# permamote.net
KiCad netlist of a schematic drawn in EAGLE
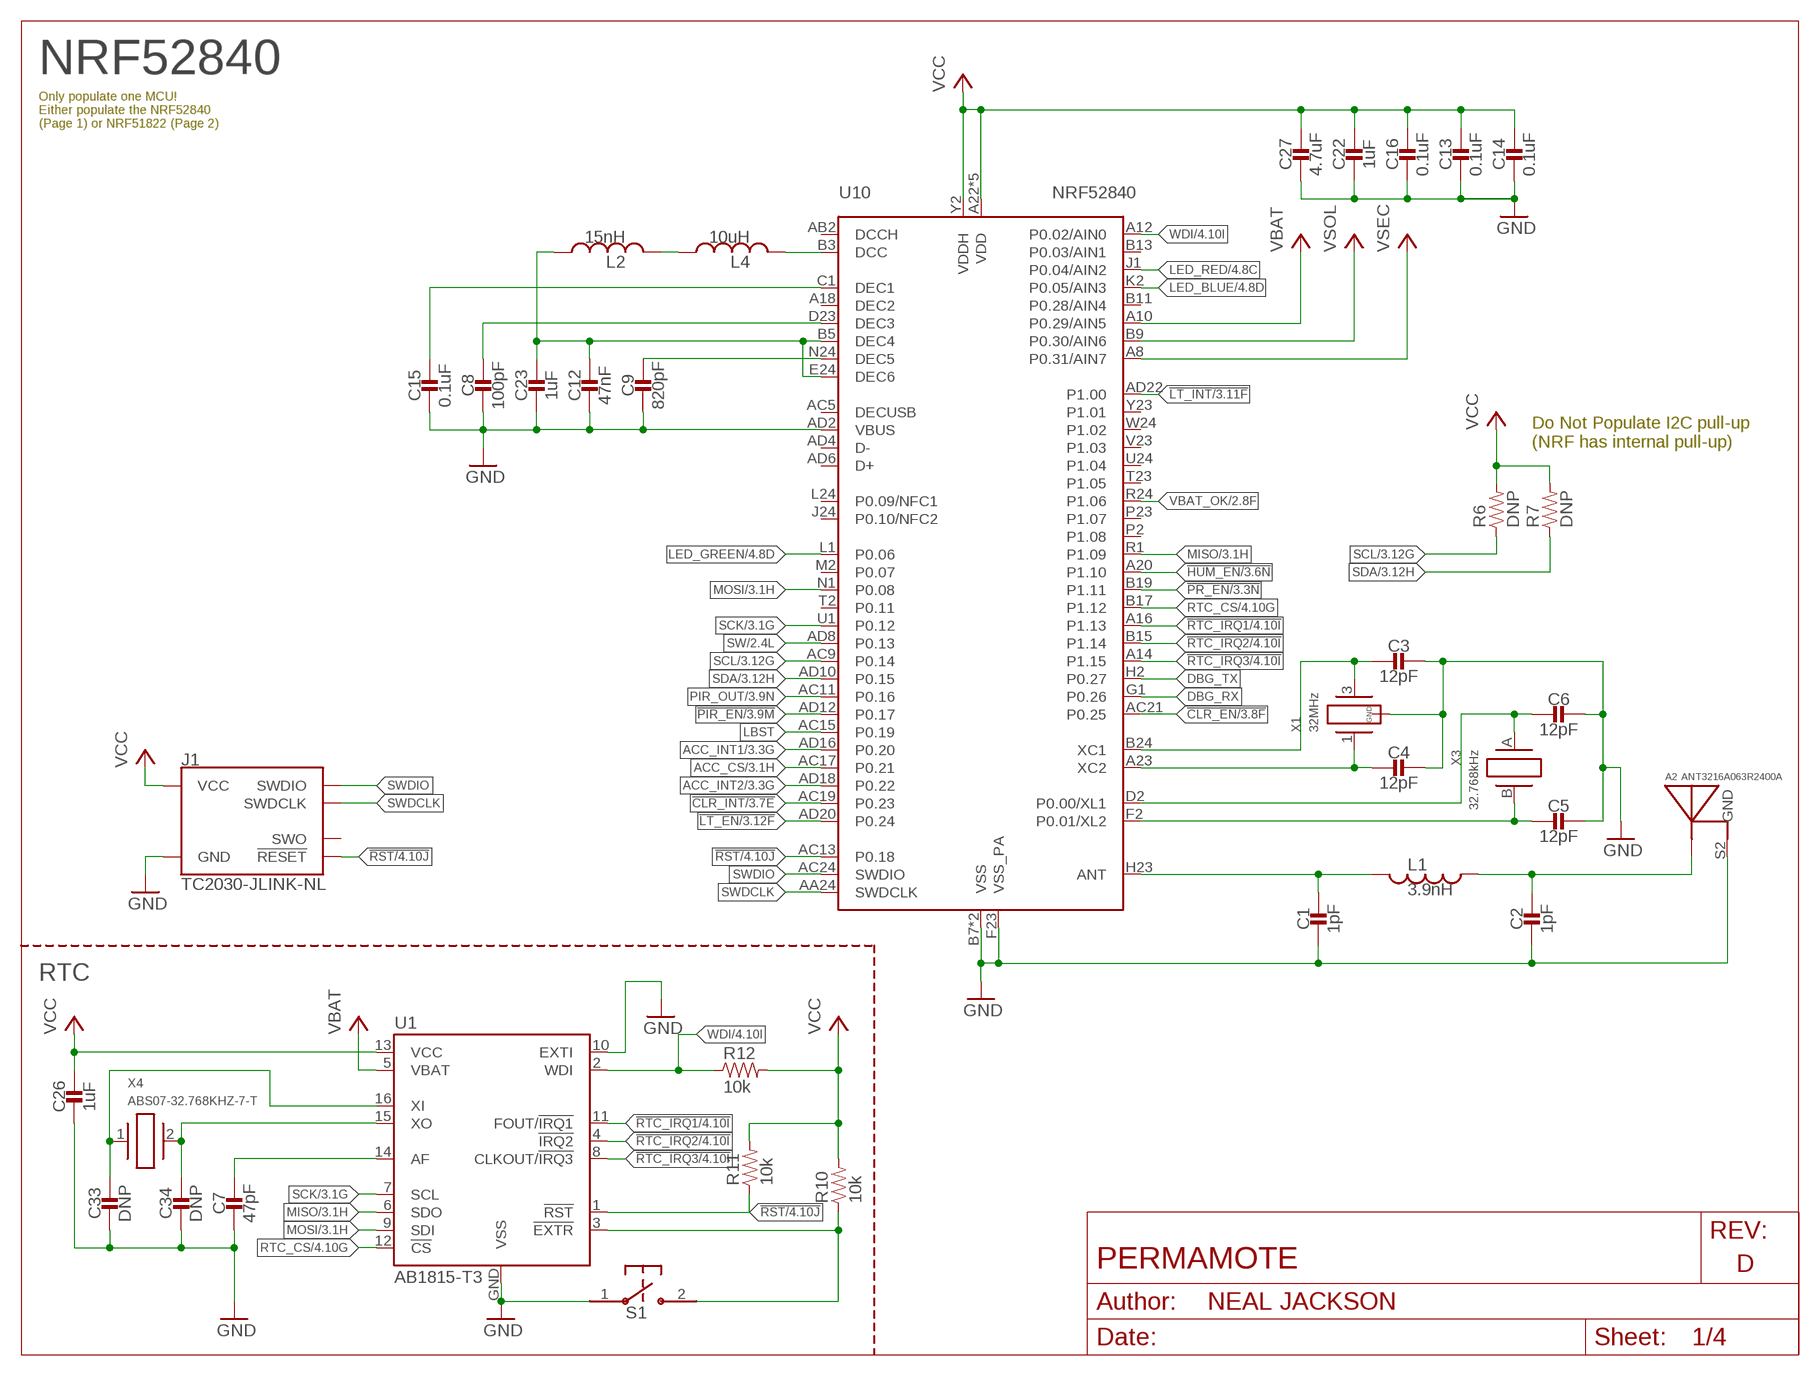
[diagram p0: schematic, sheet 1]
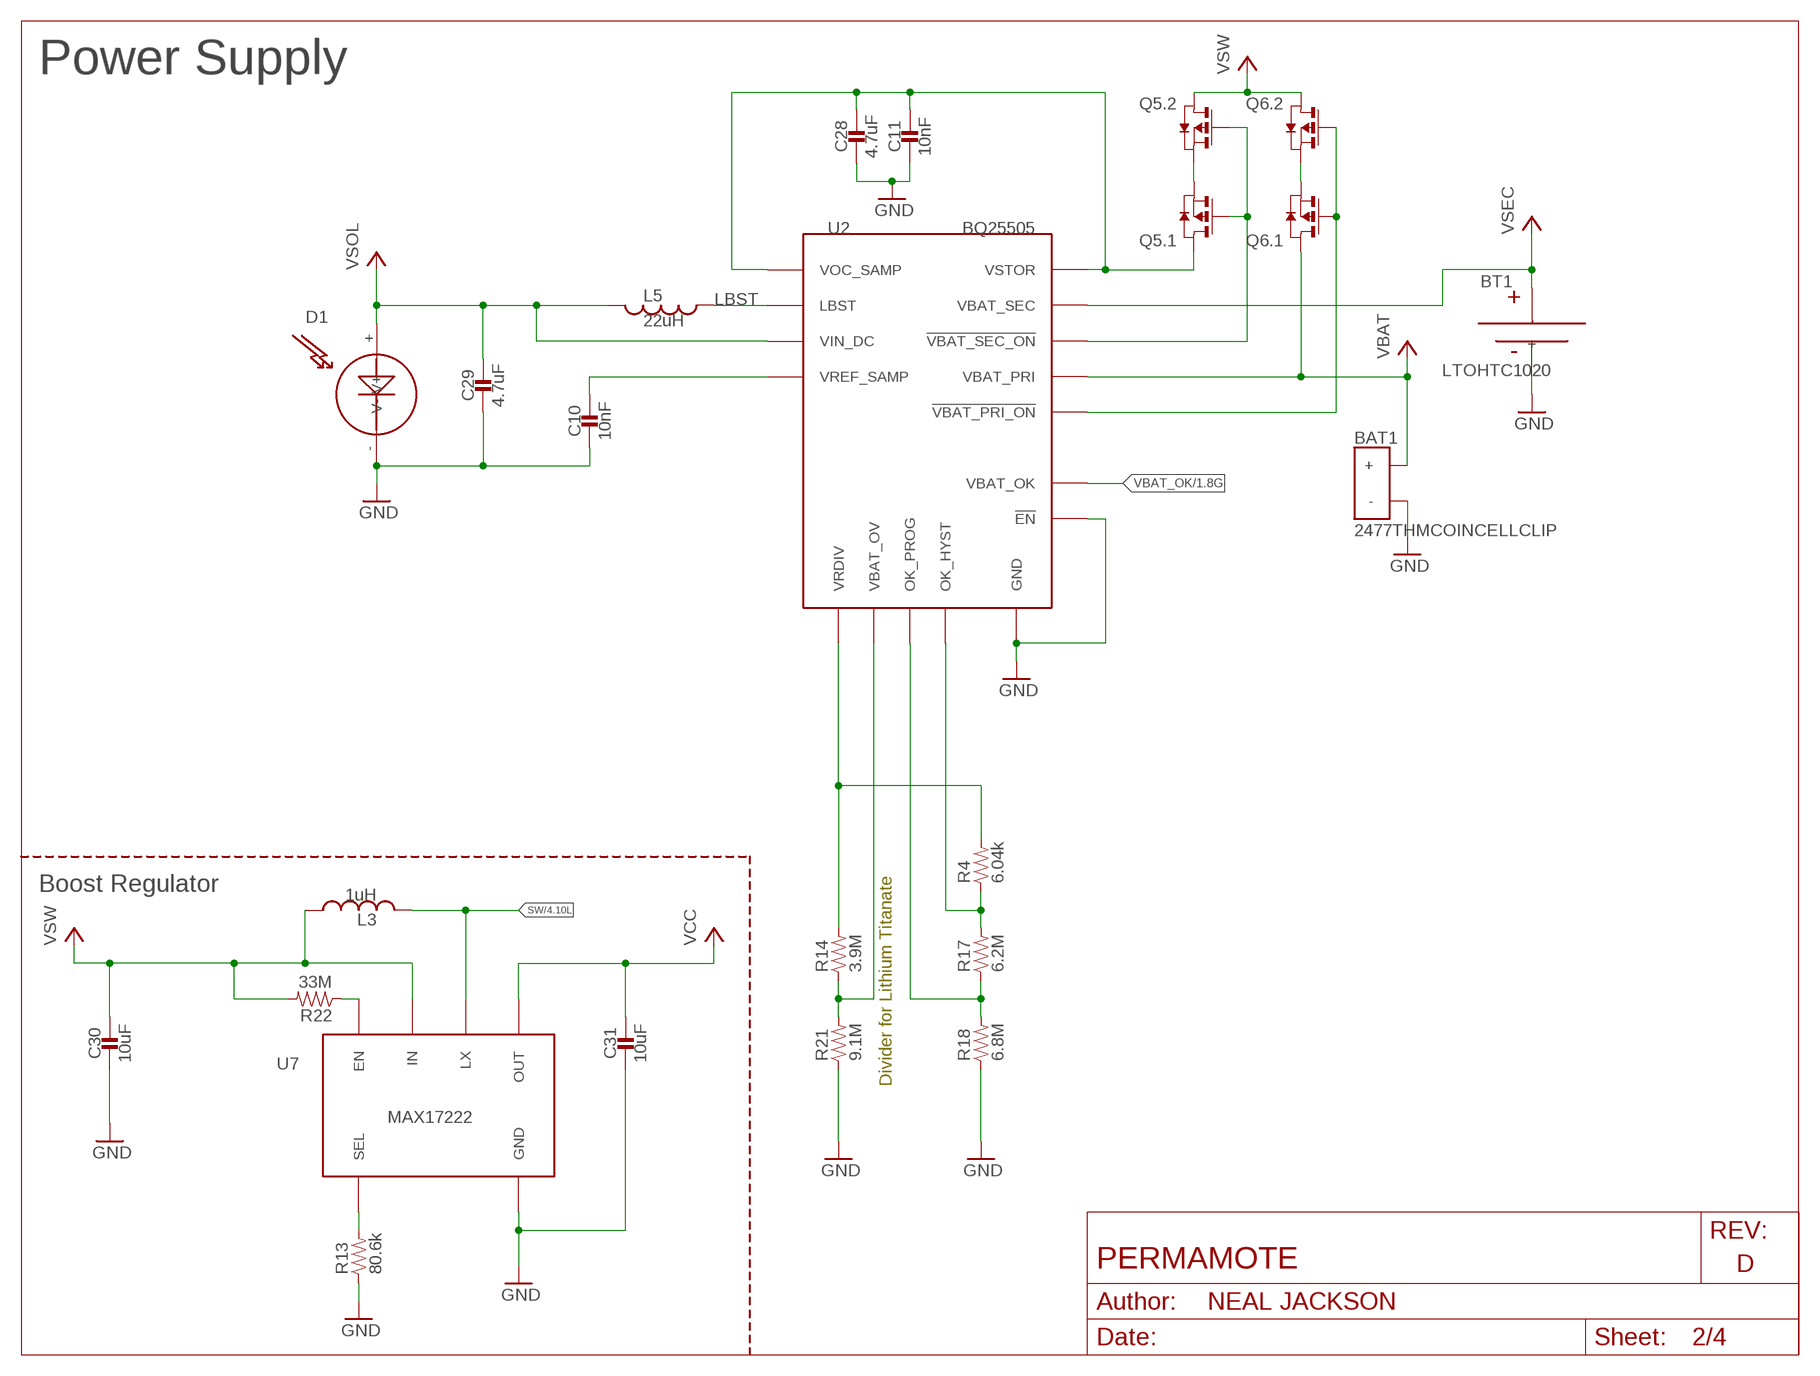
[diagram p1: schematic, sheet 2]
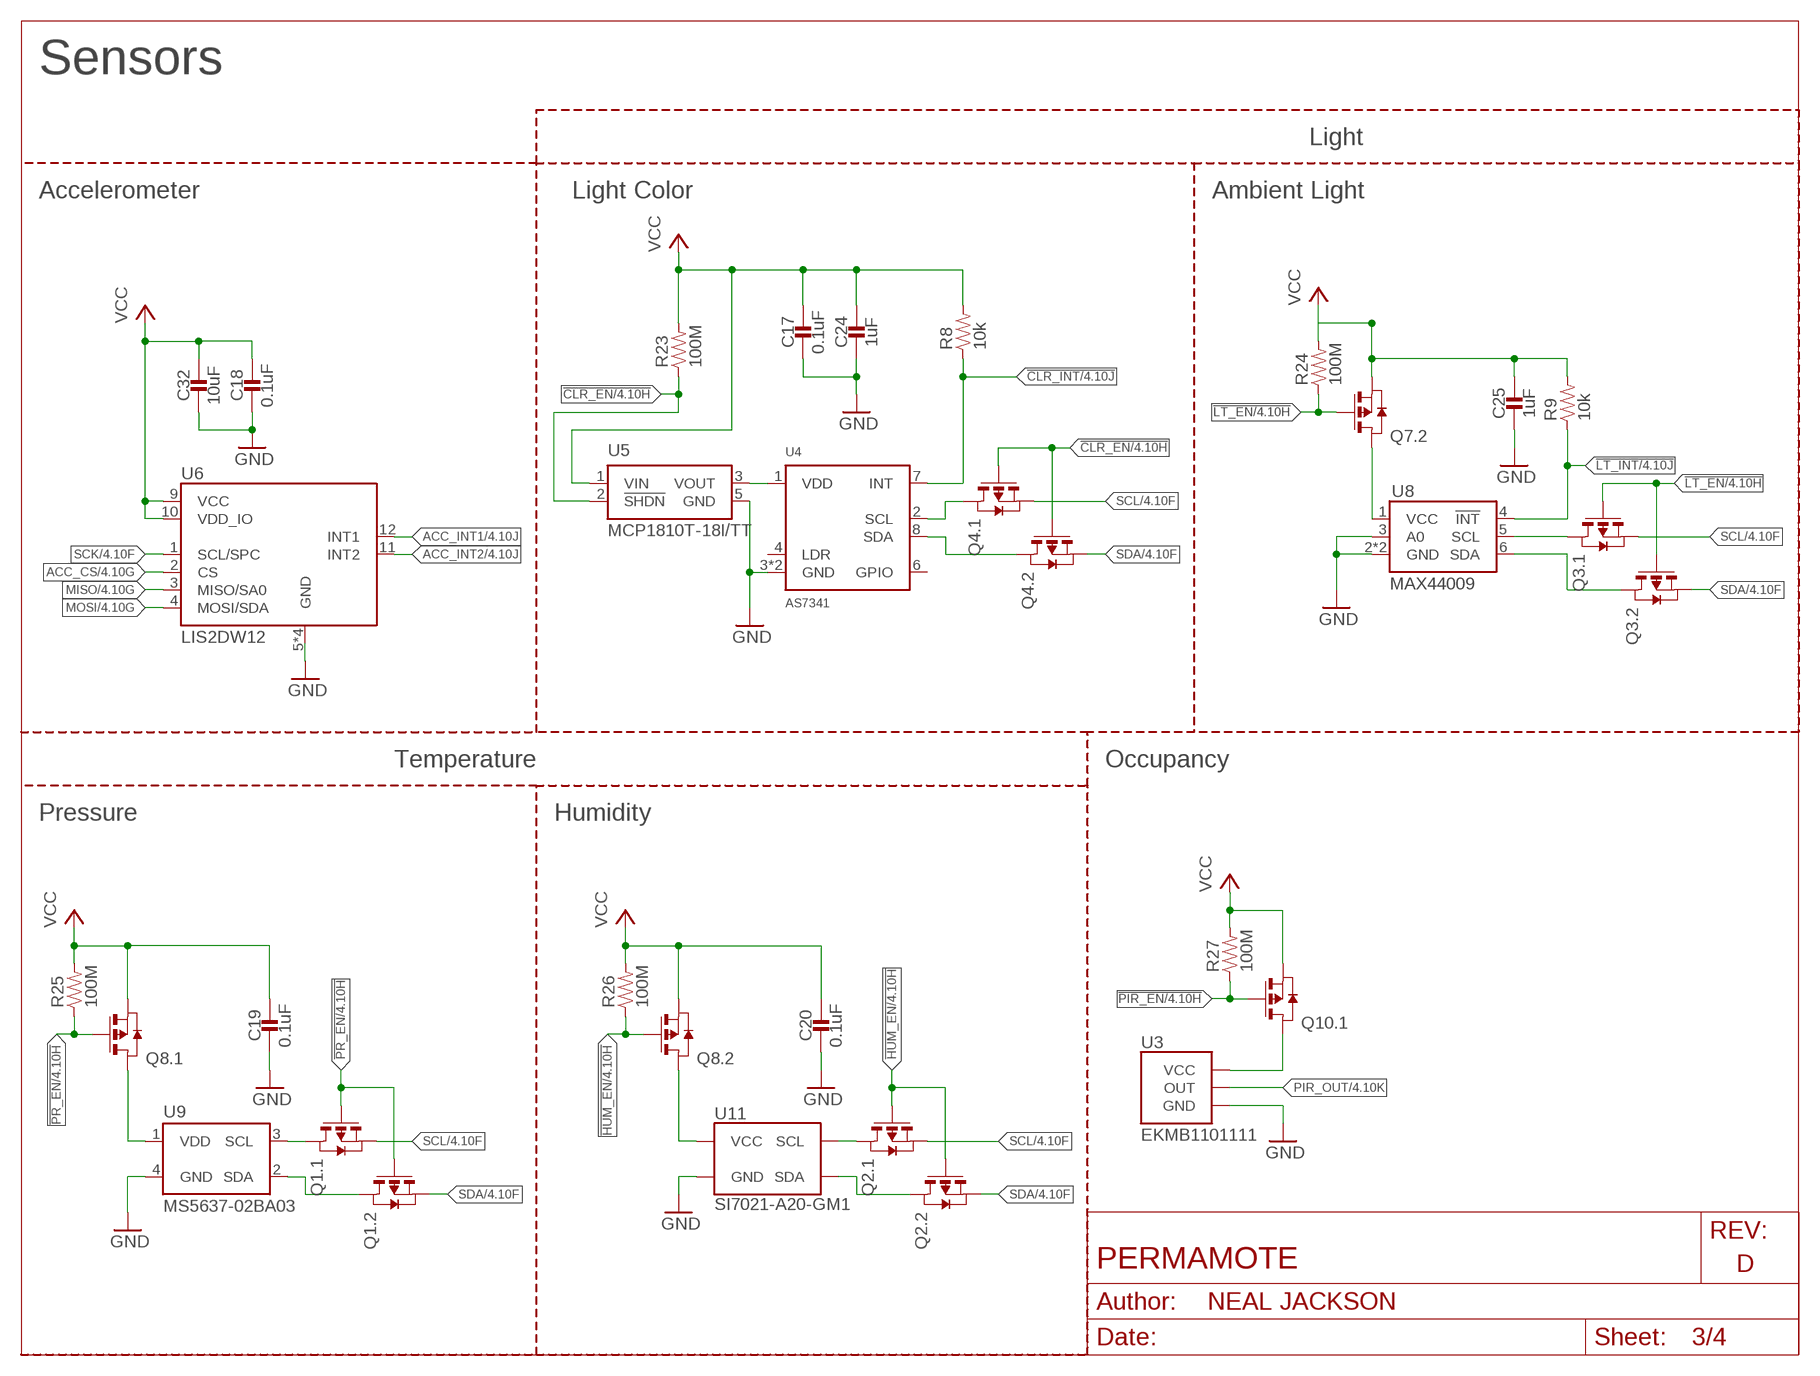
[diagram p2: schematic, sheet 3]
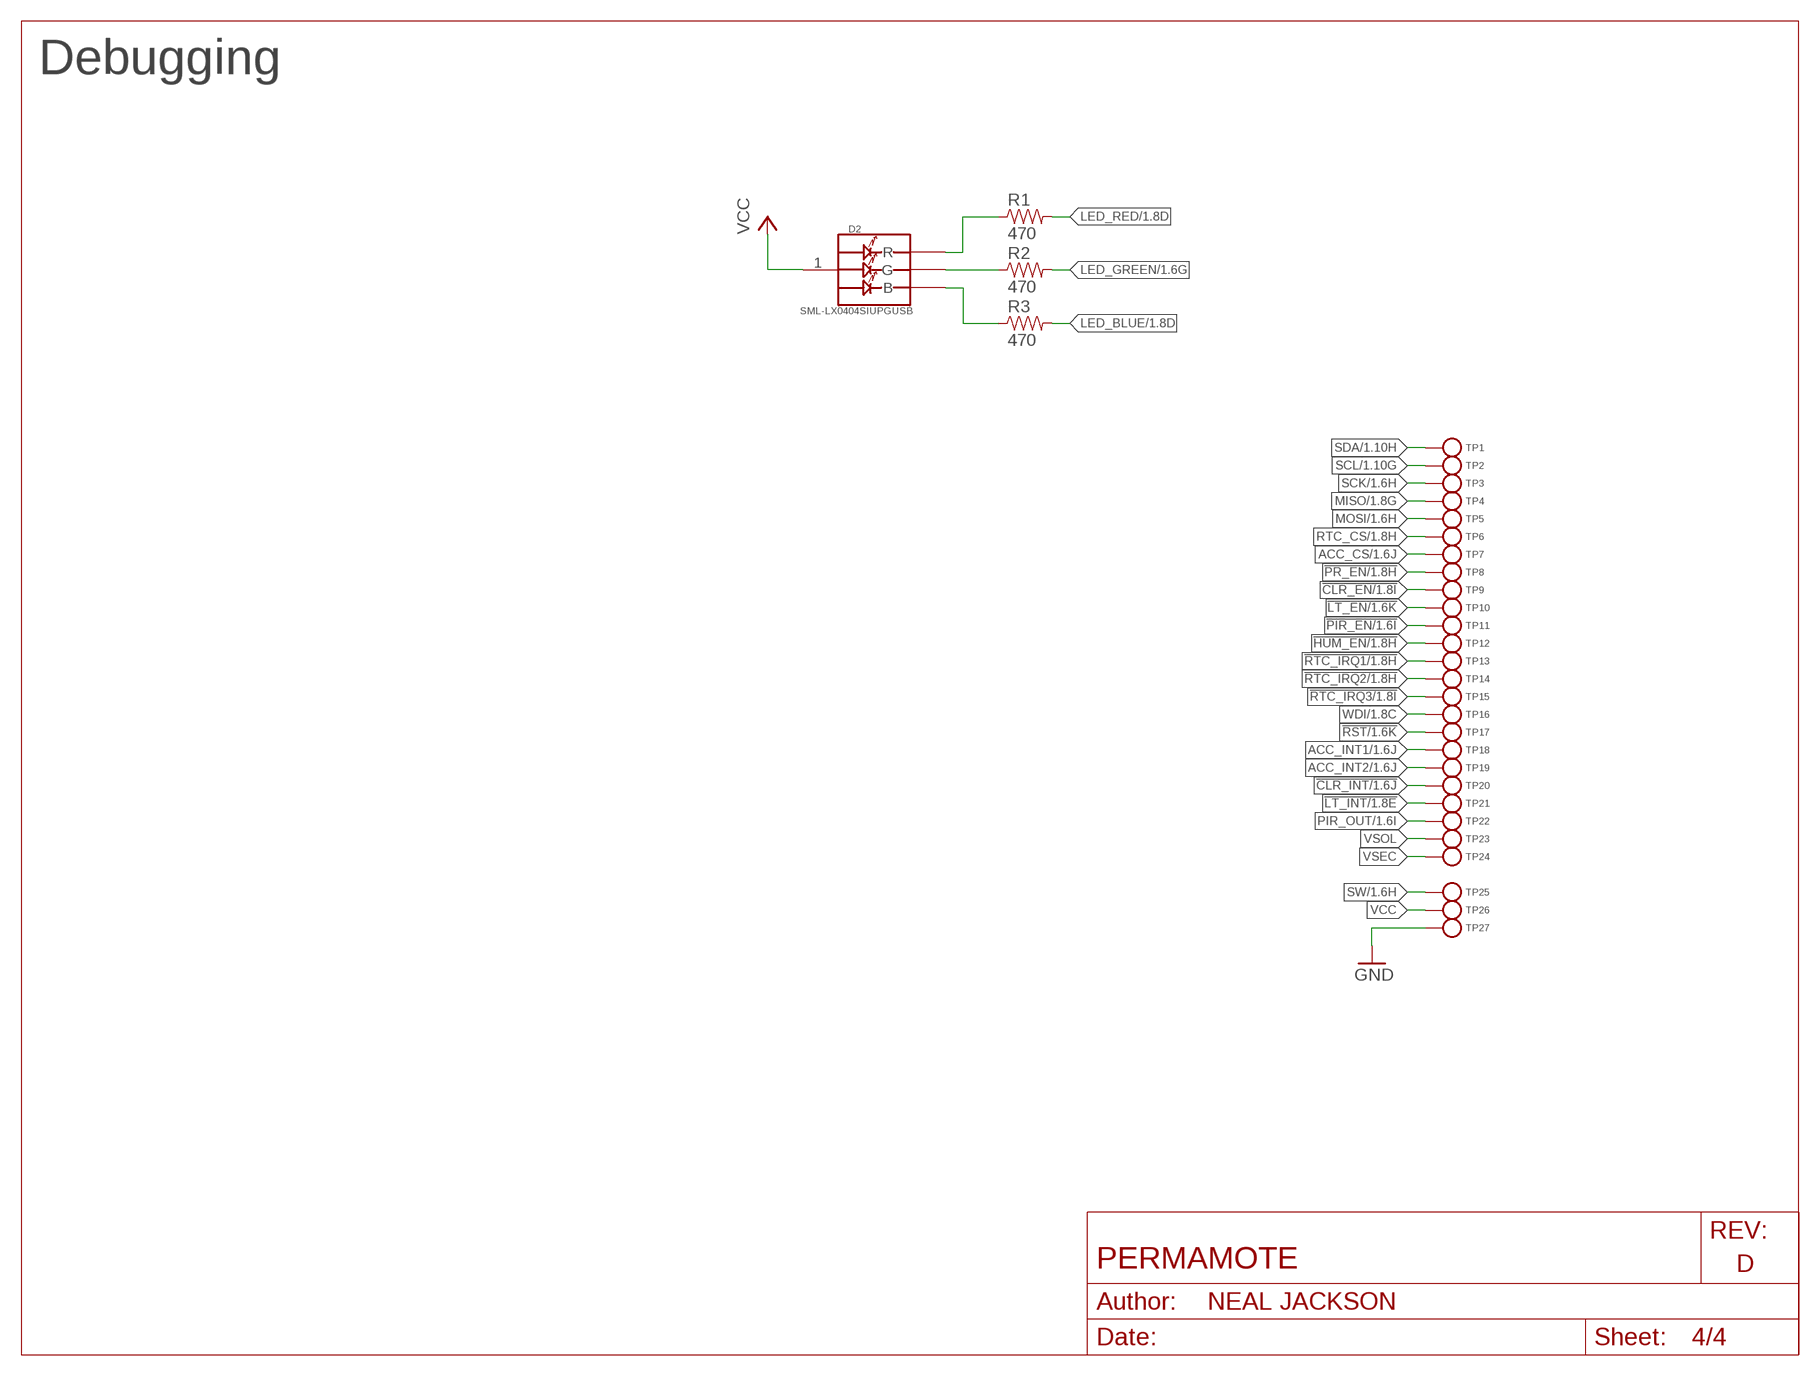
[diagram p3: schematic, sheet 4]

(export (version "E")
  (design (tool "Eeschema 10.0.6"))
  (components
    (comp (ref "BAT1")
      (value "2477THMCOINCELLCLIP")
      (footprint "eagle-import:2477THMCOINCLIP")
      (fields (field (name "MANUFACTURER") "Keystone") (field (name "MPN") "3039"))
      (libsource (lib "eagle-import") (part "2477THMCOINCELLCLIP"))
    )
    (comp (ref "BT1")
      (value "LTOHTC1020")
      (footprint "eagle-import:1020")
      (libsource (lib "eagle-import") (part "LTOHTC1020"))
    )
    (comp (ref "C10")
      (value "10nF")
      (footprint "eagle-import:0402_CAP")
      (fields (field (name "MPN") "GRM155R71H103KA88D "))
      (libsource (lib "eagle-import") (part "CAPACITOR0402_CAP"))
    )
    (comp (ref "C11")
      (value "10nF")
      (footprint "eagle-import:0402_CAP")
      (fields (field (name "MPN") "GRM155R71H103KA88D "))
      (libsource (lib "eagle-import") (part "CAPACITOR0402_CAP"))
    )
    (comp (ref "C28")
      (value "4.7uF")
      (footprint "eagle-import:0402_CAP")
      (fields (field (name "MPN") "C1005X5R0J475K050BC "))
      (libsource (lib "eagle-import") (part "CAPACITOR0402_CAP"))
    )
    (comp (ref "C29")
      (value "4.7uF")
      (footprint "eagle-import:0402_CAP")
      (fields (field (name "MPN") "C1005X5R0J475K050BC "))
      (libsource (lib "eagle-import") (part "CAPACITOR0402_CAP"))
    )
    (comp (ref "C30")
      (value "10uF")
      (footprint "eagle-import:0603_CAP")
      (fields (field (name "MPN") "GRM188R60J106ME47D "))
      (libsource (lib "eagle-import") (part "CAPACITOR0603_CAP"))
    )
    (comp (ref "C31")
      (value "10uF")
      (footprint "eagle-import:0603_CAP")
      (fields (field (name "MPN") "GRM188R60J106ME47D "))
      (libsource (lib "eagle-import") (part "CAPACITOR0603_CAP"))
    )
    (comp (ref "D1")
      (value "SOLARCELLHOLES")
      (footprint "eagle-import:SOLAR_HOLES")
      (fields (field (name "MPN") "AM-1454CA"))
      (libsource (lib "eagle-import") (part "SOLARCELLHOLES"))
    )
    (comp (ref "L3")
      (value "1uH")
      (footprint "eagle-import:IHL-1212BZ-11")
      (fields
        (field (name "MANUFACTURER") "Vishay Dale")
        (field (name "MPN") "IHLP1212BZER2R2M11")
        (field (name "DIGIKEY") "541-1319-1-ND")
        (field (name "MPN_1") "IHLP1212BZER1R0M11")
      )
      (libsource (lib "eagle-import") (part "INDUCTORIHL"))
    )
    (comp (ref "L5")
      (value "22uH")
      (footprint "eagle-import:74437324220")
      (fields (field (name "DIGIKEY") "732-3340-1-ND") (field (name "MPN") "74437324220 "))
      (libsource (lib "eagle-import") (part "INDUCTOR74437324220"))
    )
    (comp (ref "Q5")
      (value "PMDXB950UPEL")
      (footprint "eagle-import:XDFN-6")
      (fields (field (name "MANUFACTURER") "NEXPERIA") (field (name "MPN") "PMDXB950UPELZ"))
      (libsource (lib "eagle-import") (part "PMDXB950UPEL"))
    )
    (comp (ref "Q6")
      (value "PMDXB950UPEL")
      (footprint "eagle-import:XDFN-6")
      (fields (field (name "MANUFACTURER") "NEXPERIA") (field (name "MPN") "PMDXB950UPELZ"))
      (libsource (lib "eagle-import") (part "PMDXB950UPEL"))
    )
    (comp (ref "R4")
      (value "6.04k")
      (footprint "eagle-import:0402_RES")
      (fields (field (name "MPN") "RC0402FR-076K04L"))
      (libsource (lib "eagle-import") (part "RESISTOR0402_RES"))
    )
    (comp (ref "R13")
      (value "80.6k")
      (footprint "eagle-import:0603-RES")
      (fields (field (name "MPN") "RC0603FR-0780K6L "))
      (libsource (lib "eagle-import") (part "RESISTOR0603_RES"))
    )
    (comp (ref "R14")
      (value "3.9M")
      (footprint "eagle-import:0402_RES")
      (fields (field (name "MPN") "RC0402JR-073M9L"))
      (libsource (lib "eagle-import") (part "RESISTOR0402_RES"))
    )
    (comp (ref "R17")
      (value "6.2M")
      (footprint "eagle-import:0402_RES")
      (fields (field (name "MPN") "RC0402JR-076M2L"))
      (libsource (lib "eagle-import") (part "RESISTOR0402_RES"))
    )
    (comp (ref "R18")
      (value "6.8M")
      (footprint "eagle-import:0402_RES")
      (fields (field (name "MPN") "RC0402JR-076M8L"))
      (libsource (lib "eagle-import") (part "RESISTOR0402_RES"))
    )
    (comp (ref "R21")
      (value "9.1M")
      (footprint "eagle-import:0402_RES")
      (fields (field (name "MPN") "RC0402JR-079M1L"))
      (libsource (lib "eagle-import") (part "RESISTOR0402_RES"))
    )
    (comp (ref "R22")
      (value "33M")
      (footprint "eagle-import:0603-RES")
      (fields (field (name "MPN") "HMC0603JT33M0 "))
      (libsource (lib "eagle-import") (part "RESISTOR0603_RES"))
    )
    (comp (ref "U2")
      (value "BQ25505")
      (footprint "eagle-import:S-PVQFN-N20-RGR")
      (fields (field (name "MANUFACTURER") "TI") (field (name "MPN") "BQ25505RGRR"))
      (libsource (lib "eagle-import") (part "BQ25505"))
    )
    (comp (ref "U7")
      (value "MAX17222")
      (footprint "eagle-import:UDFN-6-MAXIM")
      (fields (field (name "MANUFACTURER") "MAXIM INTEGRATED") (field (name "MPN") "MAX17222ELT+T"))
      (libsource (lib "eagle-import") (part "MAX17222"))
    )
    (comp (ref "D2")
      (value "SML-LX0404SIUPGUSB")
      (footprint "eagle-import:1MM_SQ_4PAD")
      (fields (field (name "MANUFACTURER") "Lumex Opto"))
      (libsource (lib "eagle-import") (part "SML-LX0404SIUPGUSB"))
    )
    (comp (ref "R1")
      (value "470")
      (footprint "eagle-import:0402_RES")
      (fields (field (name "MPN") "RC0402JR-07470RL "))
      (libsource (lib "eagle-import") (part "RESISTOR0402_RES"))
    )
    (comp (ref "R2")
      (value "470")
      (footprint "eagle-import:0402_RES")
      (fields (field (name "MPN") "RC0402JR-07470RL "))
      (libsource (lib "eagle-import") (part "RESISTOR0402_RES"))
    )
    (comp (ref "R3")
      (value "470")
      (footprint "eagle-import:0402_RES")
      (fields (field (name "MPN") "RC0402JR-07470RL "))
      (libsource (lib "eagle-import") (part "RESISTOR0402_RES"))
    )
    (comp (ref "TP1")
      (value "TEST-POINT")
      (footprint "eagle-import:PAD.03X.03")
      (libsource (lib "eagle-import") (part "TEST-POINT"))
    )
    (comp (ref "TP2")
      (value "TEST-POINT")
      (footprint "eagle-import:PAD.03X.03")
      (libsource (lib "eagle-import") (part "TEST-POINT"))
    )
    (comp (ref "TP3")
      (value "TEST-POINT")
      (footprint "eagle-import:PAD.03X.03")
      (libsource (lib "eagle-import") (part "TEST-POINT"))
    )
    (comp (ref "TP4")
      (value "TEST-POINT")
      (footprint "eagle-import:PAD.03X.03")
      (libsource (lib "eagle-import") (part "TEST-POINT"))
    )
    (comp (ref "TP5")
      (value "TEST-POINT")
      (footprint "eagle-import:PAD.03X.03")
      (libsource (lib "eagle-import") (part "TEST-POINT"))
    )
    (comp (ref "TP6")
      (value "TEST-POINT")
      (footprint "eagle-import:PAD.03X.03")
      (libsource (lib "eagle-import") (part "TEST-POINT"))
    )
    (comp (ref "TP7")
      (value "TEST-POINT")
      (footprint "eagle-import:PAD.03X.03")
      (libsource (lib "eagle-import") (part "TEST-POINT"))
    )
    (comp (ref "TP8")
      (value "TEST-POINT")
      (footprint "eagle-import:PAD.03X.03")
      (libsource (lib "eagle-import") (part "TEST-POINT"))
    )
    (comp (ref "TP9")
      (value "TEST-POINT")
      (footprint "eagle-import:PAD.03X.03")
      (libsource (lib "eagle-import") (part "TEST-POINT"))
    )
    (comp (ref "TP10")
      (value "TEST-POINT")
      (footprint "eagle-import:PAD.03X.03")
      (libsource (lib "eagle-import") (part "TEST-POINT"))
    )
    (comp (ref "TP11")
      (value "TEST-POINT")
      (footprint "eagle-import:PAD.03X.03")
      (libsource (lib "eagle-import") (part "TEST-POINT"))
    )
    (comp (ref "TP12")
      (value "TEST-POINT")
      (footprint "eagle-import:PAD.03X.03")
      (libsource (lib "eagle-import") (part "TEST-POINT"))
    )
    (comp (ref "TP13")
      (value "TEST-POINT")
      (footprint "eagle-import:PAD.03X.03")
      (libsource (lib "eagle-import") (part "TEST-POINT"))
    )
    (comp (ref "TP14")
      (value "TEST-POINT")
      (footprint "eagle-import:PAD.03X.03")
      (libsource (lib "eagle-import") (part "TEST-POINT"))
    )
    (comp (ref "TP15")
      (value "TEST-POINT")
      (footprint "eagle-import:PAD.03X.03")
      (libsource (lib "eagle-import") (part "TEST-POINT"))
    )
    (comp (ref "TP16")
      (value "TEST-POINT")
      (footprint "eagle-import:PAD.03X.03")
      (libsource (lib "eagle-import") (part "TEST-POINT"))
    )
    (comp (ref "TP17")
      (value "TEST-POINT")
      (footprint "eagle-import:PAD.03X.03")
      (libsource (lib "eagle-import") (part "TEST-POINT"))
    )
    (comp (ref "TP18")
      (value "TEST-POINT")
      (footprint "eagle-import:PAD.03X.03")
      (libsource (lib "eagle-import") (part "TEST-POINT"))
    )
    (comp (ref "TP19")
      (value "TEST-POINT")
      (footprint "eagle-import:PAD.03X.03")
      (libsource (lib "eagle-import") (part "TEST-POINT"))
    )
    (comp (ref "TP20")
      (value "TEST-POINT")
      (footprint "eagle-import:PAD.03X.03")
      (libsource (lib "eagle-import") (part "TEST-POINT"))
    )
    (comp (ref "TP21")
      (value "TEST-POINT")
      (footprint "eagle-import:PAD.03X.03")
      (libsource (lib "eagle-import") (part "TEST-POINT"))
    )
    (comp (ref "TP22")
      (value "TEST-POINT")
      (footprint "eagle-import:PAD.03X.03")
      (libsource (lib "eagle-import") (part "TEST-POINT"))
    )
    (comp (ref "TP23")
      (value "TEST-POINT")
      (footprint "eagle-import:PAD.03X.03")
      (libsource (lib "eagle-import") (part "TEST-POINT"))
    )
    (comp (ref "TP24")
      (value "TEST-POINT")
      (footprint "eagle-import:PAD.03X.03")
      (libsource (lib "eagle-import") (part "TEST-POINT"))
    )
    (comp (ref "TP25")
      (value "TEST-POINT")
      (footprint "eagle-import:PAD.03X.03")
      (libsource (lib "eagle-import") (part "TEST-POINT"))
    )
    (comp (ref "TP26")
      (value "TEST-POINT")
      (footprint "eagle-import:PAD.03X.03")
      (libsource (lib "eagle-import") (part "TEST-POINT"))
    )
    (comp (ref "TP27")
      (value "TEST-POINT")
      (footprint "eagle-import:PAD.03X.03")
      (libsource (lib "eagle-import") (part "TEST-POINT"))
    )
    (comp (ref "C17")
      (value "0.1uF")
      (footprint "eagle-import:0402_CAP")
      (fields (field (name "MPN") "GRM155R71C104KA88J "))
      (libsource (lib "eagle-import") (part "CAPACITOR0402_CAP"))
    )
    (comp (ref "C18")
      (value "0.1uF")
      (footprint "eagle-import:0402_CAP")
      (fields (field (name "MPN") "GRM155R71C104KA88J "))
      (libsource (lib "eagle-import") (part "CAPACITOR0402_CAP"))
    )
    (comp (ref "C19")
      (value "0.1uF")
      (footprint "eagle-import:0402_CAP")
      (fields (field (name "MPN") "GRM155R71C104KA88J "))
      (libsource (lib "eagle-import") (part "CAPACITOR0402_CAP"))
    )
    (comp (ref "C20")
      (value "0.1uF")
      (footprint "eagle-import:0402_CAP")
      (fields (field (name "MPN") "GRM155R71C104KA88J "))
      (libsource (lib "eagle-import") (part "CAPACITOR0402_CAP"))
    )
    (comp (ref "C24")
      (value "1uF")
      (footprint "eagle-import:0402_CAP")
      (fields (field (name "MPN") "GRM155R70G105KA12D "))
      (libsource (lib "eagle-import") (part "CAPACITOR0402_CAP"))
    )
    (comp (ref "C25")
      (value "1uF")
      (footprint "eagle-import:0402_CAP")
      (fields (field (name "MPN") "GRM155R70G105KA12D "))
      (libsource (lib "eagle-import") (part "CAPACITOR0402_CAP"))
    )
    (comp (ref "C32")
      (value "10uF")
      (footprint "eagle-import:0603_CAP")
      (fields (field (name "MPN") "GRM188R60J106ME47D "))
      (libsource (lib "eagle-import") (part "CAPACITOR0603_CAP"))
    )
    (comp (ref "Q1")
      (value "PMDXB950UPEL")
      (footprint "eagle-import:XDFN-6")
      (fields (field (name "MANUFACTURER") "NEXPERIA") (field (name "MPN") "PMDXB950UPELZ"))
      (libsource (lib "eagle-import") (part "PMDXB950UPEL"))
    )
    (comp (ref "Q2")
      (value "PMDXB950UPEL")
      (footprint "eagle-import:XDFN-6")
      (fields (field (name "MANUFACTURER") "NEXPERIA") (field (name "MPN") "PMDXB950UPELZ"))
      (libsource (lib "eagle-import") (part "PMDXB950UPEL"))
    )
    (comp (ref "Q3")
      (value "PMDXB950UPEL")
      (footprint "eagle-import:XDFN-6")
      (fields (field (name "MANUFACTURER") "NEXPERIA") (field (name "MPN") "PMDXB950UPELZ"))
      (libsource (lib "eagle-import") (part "PMDXB950UPEL"))
    )
    (comp (ref "Q4")
      (value "PMDXB950UPEL")
      (footprint "eagle-import:XDFN-6")
      (fields (field (name "MANUFACTURER") "NEXPERIA") (field (name "MPN") "PMDXB950UPELZ"))
      (libsource (lib "eagle-import") (part "PMDXB950UPEL"))
    )
    (comp (ref "Q7")
      (value "PMDXB950UPEL")
      (footprint "eagle-import:XDFN-6")
      (fields (field (name "MANUFACTURER") "NEXPERIA") (field (name "MPN") "PMDXB950UPELZ"))
      (libsource (lib "eagle-import") (part "PMDXB950UPEL"))
    )
    (comp (ref "Q8")
      (value "PMDXB950UPEL")
      (footprint "eagle-import:XDFN-6")
      (fields (field (name "MANUFACTURER") "NEXPERIA") (field (name "MPN") "PMDXB950UPELZ"))
      (libsource (lib "eagle-import") (part "PMDXB950UPEL"))
    )
    (comp (ref "Q10")
      (value "PMDXB950UPEL")
      (footprint "eagle-import:XDFN-6")
      (fields (field (name "MANUFACTURER") "NEXPERIA") (field (name "MPN") "PMDXB950UPELZ"))
      (libsource (lib "eagle-import") (part "PMDXB950UPEL"))
    )
    (comp (ref "R8")
      (value "10k")
      (footprint "eagle-import:0402_RES")
      (fields (field (name "MPN") "RC0402JR-0710KL"))
      (libsource (lib "eagle-import") (part "RESISTOR0402_RES"))
    )
    (comp (ref "R9")
      (value "10k")
      (footprint "eagle-import:0402_RES")
      (fields (field (name "MPN") "RC0402JR-0710KL"))
      (libsource (lib "eagle-import") (part "RESISTOR0402_RES"))
    )
    (comp (ref "R23")
      (value "100M")
      (footprint "eagle-import:0402_RES")
      (fields (field (name "MPN") "HMC0402JT100M "))
      (libsource (lib "eagle-import") (part "RESISTOR0402_RES"))
    )
    (comp (ref "R24")
      (value "100M")
      (footprint "eagle-import:0402_RES")
      (fields (field (name "MPN") "HMC0402JT100M "))
      (libsource (lib "eagle-import") (part "RESISTOR0402_RES"))
    )
    (comp (ref "R25")
      (value "100M")
      (footprint "eagle-import:0402_RES")
      (fields (field (name "MPN") "HMC0402JT100M "))
      (libsource (lib "eagle-import") (part "RESISTOR0402_RES"))
    )
    (comp (ref "R26")
      (value "100M")
      (footprint "eagle-import:0402_RES")
      (fields (field (name "MPN") "HMC0402JT100M "))
      (libsource (lib "eagle-import") (part "RESISTOR0402_RES"))
    )
    (comp (ref "R27")
      (value "100M")
      (footprint "eagle-import:0402_RES")
      (fields (field (name "MPN") "HMC0402JT100M "))
      (libsource (lib "eagle-import") (part "RESISTOR0402_RES"))
    )
    (comp (ref "U3")
      (value "EKMB1101111")
      (footprint "eagle-import:AMN2")
      (fields (field (name "MANUFACTURER") "PANASONIC"))
      (libsource (lib "eagle-import") (part "EKMB1101111"))
    )
    (comp (ref "U4")
      (value "AS7341")
      (footprint "eagle-import:OLGA-8")
      (libsource (lib "eagle-import") (part "AS7341"))
    )
    (comp (ref "U5")
      (value "MCP1810T-18I/TT")
      (footprint "eagle-import:SOT-23-5")
      (libsource (lib "eagle-import") (part "MCP1810T-18I/TT"))
    )
    (comp (ref "U6")
      (value "LIS2DW12")
      (footprint "eagle-import:LGA-12")
      (fields (field (name "MANUFACTURER") "STMicroelectronics") (field (name "MPN") "LIS2DW12TR"))
      (libsource (lib "eagle-import") (part "LIS2DW12"))
    )
    (comp (ref "U8")
      (value "MAX44009")
      (footprint "eagle-import:UDFN-6-EXPOSED")
      (fields (field (name "MANUFACTURER") "MAXIM") (field (name "MPN") "MAX44009EDT+T"))
      (libsource (lib "eagle-import") (part "MAX44009"))
    )
    (comp (ref "U9")
      (value "MS5637-02BA03")
      (footprint "eagle-import:4-SMD")
      (fields (field (name "MANUFACTURER") "TE CONNECTIVITY") (field (name "MPN") "MS563702BA03-50"))
      (libsource (lib "eagle-import") (part "MS5637-02BA03"))
    )
    (comp (ref "U11")
      (value "SI7021-A20-GM1")
      (footprint "eagle-import:DFN-6_3MM")
      (fields (field (name "MPN") "SI7021-A20-GM1 "))
      (libsource (lib "eagle-import") (part "SI7021-A20-GM1"))
    )
    (comp (ref "A2")
      (value "ANT3216A063R2400A")
      (footprint "eagle-import:ANT3216A063R2400A")
      (fields (field (name "MANUFACTURER") "YAGEO"))
      (libsource (lib "eagle-import") (part "ANT3216A063R2400A"))
    )
    (comp (ref "C1")
      (value "1pF")
      (footprint "eagle-import:0402_CAP")
      (fields (field (name "MPN") "CL05C010CB5NNNC"))
      (libsource (lib "eagle-import") (part "CAPACITOR0402_CAP"))
    )
    (comp (ref "C2")
      (value "1pF")
      (footprint "eagle-import:0402_CAP")
      (fields (field (name "MPN") "CL05C010CB5NNNC"))
      (libsource (lib "eagle-import") (part "CAPACITOR0402_CAP"))
    )
    (comp (ref "C3")
      (value "12pF")
      (footprint "eagle-import:0402_CAP")
      (fields (field (name "MPN") "GRM1555C1H120GA01D "))
      (libsource (lib "eagle-import") (part "CAPACITOR0402_CAP"))
    )
    (comp (ref "C4")
      (value "12pF")
      (footprint "eagle-import:0402_CAP")
      (fields (field (name "MPN") "GRM1555C1H120GA01D "))
      (libsource (lib "eagle-import") (part "CAPACITOR0402_CAP"))
    )
    (comp (ref "C5")
      (value "12pF")
      (footprint "eagle-import:0402_CAP")
      (fields (field (name "MPN") "GRM1555C1H120GA01D "))
      (libsource (lib "eagle-import") (part "CAPACITOR0402_CAP"))
    )
    (comp (ref "C6")
      (value "12pF")
      (footprint "eagle-import:0402_CAP")
      (fields (field (name "MPN") "GRM1555C1H120GA01D "))
      (libsource (lib "eagle-import") (part "CAPACITOR0402_CAP"))
    )
    (comp (ref "C7")
      (value "47pF")
      (footprint "eagle-import:0402_CAP")
      (fields (field (name "MPN") "GRM1555C1H470JA01D "))
      (libsource (lib "eagle-import") (part "CAPACITOR0402_CAP"))
    )
    (comp (ref "C8")
      (value "100pF")
      (footprint "eagle-import:0402_CAP")
      (fields (field (name "MPN") "GRM1555C1H101JA01D "))
      (libsource (lib "eagle-import") (part "CAPACITOR0402_CAP"))
    )
    (comp (ref "C9")
      (value "820pF")
      (footprint "eagle-import:0402_CAP")
      (fields (field (name "MPN") "CL05B821KO5NNNC"))
      (libsource (lib "eagle-import") (part "CAPACITOR0402_CAP"))
    )
    (comp (ref "C12")
      (value "47nF")
      (footprint "eagle-import:0402_CAP")
      (fields (field (name "MPN") "C1005X7R1C473K050BC "))
      (libsource (lib "eagle-import") (part "CAPACITOR0402_CAP"))
    )
    (comp (ref "C13")
      (value "0.1uF")
      (footprint "eagle-import:0402_CAP")
      (fields (field (name "MPN") "GRM155R71C104KA88J "))
      (libsource (lib "eagle-import") (part "CAPACITOR0402_CAP"))
    )
    (comp (ref "C14")
      (value "0.1uF")
      (footprint "eagle-import:0402_CAP")
      (fields (field (name "MPN") "GRM155R71C104KA88J "))
      (libsource (lib "eagle-import") (part "CAPACITOR0402_CAP"))
    )
    (comp (ref "C15")
      (value "0.1uF")
      (footprint "eagle-import:0402_CAP")
      (fields (field (name "MPN") "GRM155R71C104KA88J "))
      (libsource (lib "eagle-import") (part "CAPACITOR0402_CAP"))
    )
    (comp (ref "C16")
      (value "0.1uF")
      (footprint "eagle-import:0402_CAP")
      (fields (field (name "MPN") "GRM155R71C104KA88J "))
      (libsource (lib "eagle-import") (part "CAPACITOR0402_CAP"))
    )
    (comp (ref "C22")
      (value "1uF")
      (footprint "eagle-import:0402_CAP")
      (fields (field (name "MPN") "GRM155R70G105KA12D "))
      (libsource (lib "eagle-import") (part "CAPACITOR0402_CAP"))
    )
    (comp (ref "C23")
      (value "1uF")
      (footprint "eagle-import:0402_CAP")
      (fields (field (name "MPN") "GRM155R70G105KA12D "))
      (libsource (lib "eagle-import") (part "CAPACITOR0402_CAP"))
    )
    (comp (ref "C26")
      (value "1uF")
      (footprint "eagle-import:0402_CAP")
      (fields (field (name "MPN") "GRM155R70G105KA12D "))
      (libsource (lib "eagle-import") (part "CAPACITOR0402_CAP"))
    )
    (comp (ref "C27")
      (value "4.7uF")
      (footprint "eagle-import:0402_CAP")
      (fields (field (name "MPN") "C1005X5R0J475K050BC "))
      (libsource (lib "eagle-import") (part "CAPACITOR0402_CAP"))
    )
    (comp (ref "C33")
      (value "DNP")
      (footprint "eagle-import:0402_CAP")
      (libsource (lib "eagle-import") (part "CAPACITOR0402_CAP"))
    )
    (comp (ref "C34")
      (value "DNP")
      (footprint "eagle-import:0402_CAP")
      (libsource (lib "eagle-import") (part "CAPACITOR0402_CAP"))
    )
    (comp (ref "J1")
      (value "TC2030-JLINK-NL")
      (footprint "eagle-import:TC2030-IDC-NL")
      (libsource (lib "eagle-import") (part "TC2030-JLINK-NL"))
    )
    (comp (ref "L1")
      (value "3.9nH")
      (footprint "eagle-import:0402_CAP")
      (fields (field (name "MPN") "LQP15MN3N9B02D"))
      (libsource (lib "eagle-import") (part "INDUCTOR0402"))
    )
    (comp (ref "L2")
      (value "15nH")
      (footprint "eagle-import:0402_CAP")
      (fields (field (name "MPN") "HK100515NJ-T "))
      (libsource (lib "eagle-import") (part "INDUCTOR0402"))
    )
    (comp (ref "L4")
      (value "10uH")
      (footprint "eagle-import:0603_CAP")
      (fields (field (name "MPN") "LQM18FN100M00D "))
      (libsource (lib "eagle-import") (part "INDUCTOR0603"))
    )
    (comp (ref "R6")
      (value "DNP")
      (footprint "eagle-import:0402_RES")
      (fields (field (name "MPN") "RC0402JR-0710KL"))
      (libsource (lib "eagle-import") (part "RESISTOR0402_RES"))
    )
    (comp (ref "R7")
      (value "DNP")
      (footprint "eagle-import:0402_RES")
      (fields (field (name "MPN") "RC0402JR-0710KL"))
      (libsource (lib "eagle-import") (part "RESISTOR0402_RES"))
    )
    (comp (ref "R10")
      (value "10k")
      (footprint "eagle-import:0402_RES")
      (fields (field (name "MPN") "RC0402JR-0710KL"))
      (libsource (lib "eagle-import") (part "RESISTOR0402_RES"))
    )
    (comp (ref "R11")
      (value "10k")
      (footprint "eagle-import:0402_RES")
      (fields (field (name "MPN") "RC0402JR-0710KL"))
      (libsource (lib "eagle-import") (part "RESISTOR0402_RES"))
    )
    (comp (ref "R12")
      (value "10k")
      (footprint "eagle-import:0402_RES")
      (fields (field (name "MPN") "RC0402JR-0710KL"))
      (libsource (lib "eagle-import") (part "RESISTOR0402_RES"))
    )
    (comp (ref "S1")
      (value "B3U-1000P")
      (footprint "eagle-import:B3U-1000P")
      (fields (field (name "MANUFACTURER") "Omron"))
      (libsource (lib "eagle-import") (part "B3U-1000P"))
    )
    (comp (ref "U1")
      (value "AB1815-T3")
      (footprint "eagle-import:QFN-16-3MM")
      (fields (field (name "MANUFACTURER") "Abracon"))
      (libsource (lib "eagle-import") (part "AB1815-T3"))
    )
    (comp (ref "U10")
      (value "NRF52840")
      (footprint "eagle-import:AQFN73")
      (fields (field (name "MANUFACTURER") "NORIDIC SEMICONDUCTOR"))
      (libsource (lib "eagle-import") (part "NRF52840"))
    )
    (comp (ref "X1")
      (value "32MHz")
      (footprint "eagle-import:TXC-7V")
      (fields (field (name "MANUFACTURER") "TXC CORPORATION") (field (name "MPN") "7M-32.000MAHV-T"))
      (libsource (lib "eagle-import") (part "7V-32.000MAHV-T"))
    )
    (comp (ref "X3")
      (value "32.768kHz")
      (footprint "eagle-import:ABS05")
      (fields (field (name "MANUFACTURER") "Abracon") (field (name "MPN") "ABS05-32.768KHZ-9-T"))
      (libsource (lib "eagle-import") (part "ABS05-32.768KHZ-9-T"))
    )
    (comp (ref "X4")
      (value "ABS07-32.768KHZ-7-T")
      (footprint "eagle-import:2-SMD")
      (fields (field (name "MANUFACTURER") "ABRACON") (field (name "MPN") "ABS07-32.768KHZ-7-T "))
      (libsource (lib "eagle-import") (part "ABS07-32.768KHZ-7-T"))
    )
  )
  (nets
    (net (code "1") (name "ACC_CS") (class "Default")
      (node (ref "TP7") (pin "P$1") (pinfunction "TESTPOINT_P$1") (pintype "bidirectional"))
      (node (ref "U10") (pin "AC17") (pinfunction "P0.21_AC17") (pintype "bidirectional"))
      (node (ref "U6") (pin "2") (pinfunction "CS_2") (pintype "bidirectional"))
    )
    (net (code "2") (name "ACC_INT1") (class "Default")
      (node (ref "TP18") (pin "P$1") (pinfunction "TESTPOINT_P$1") (pintype "bidirectional"))
      (node (ref "U10") (pin "AD16") (pinfunction "P0.20_AD16") (pintype "bidirectional"))
      (node (ref "U6") (pin "12") (pinfunction "INT1_12") (pintype "bidirectional"))
    )
    (net (code "3") (name "ACC_INT2") (class "Default")
      (node (ref "TP19") (pin "P$1") (pinfunction "TESTPOINT_P$1") (pintype "bidirectional"))
      (node (ref "U10") (pin "AD18") (pinfunction "P0.22_AD18") (pintype "bidirectional"))
      (node (ref "U6") (pin "11") (pinfunction "INT2_11") (pintype "bidirectional"))
    )
    (net (code "4") (name "DBG_RX") (class "Default")
      (node (ref "U10") (pin "G1") (pinfunction "P0.26_G1") (pintype "bidirectional"))
    )
    (net (code "5") (name "DBG_TX") (class "Default")
      (node (ref "U10") (pin "H2") (pinfunction "P0.27_H2") (pintype "bidirectional"))
    )
    (net (code "6") (name "GND") (class "Default")
      (node (ref "A2") (pin "S2") (pinfunction "GND_S2") (pintype "bidirectional"))
      (node (ref "BAT1") (pin "GND") (pinfunction "-_GND") (pintype "bidirectional"))
      (node (ref "BT1") (pin "-") (pinfunction "-_-") (pintype "bidirectional"))
      (node (ref "C1") (pin "2") (pinfunction "2_2") (pintype "bidirectional"))
      (node (ref "C10") (pin "2") (pinfunction "2_2") (pintype "bidirectional"))
      (node (ref "C11") (pin "2") (pinfunction "2_2") (pintype "bidirectional"))
      (node (ref "C12") (pin "2") (pinfunction "2_2") (pintype "bidirectional"))
      (node (ref "C13") (pin "2") (pinfunction "2_2") (pintype "bidirectional"))
      (node (ref "C14") (pin "2") (pinfunction "2_2") (pintype "bidirectional"))
      (node (ref "C15") (pin "2") (pinfunction "2_2") (pintype "bidirectional"))
      (node (ref "C16") (pin "2") (pinfunction "2_2") (pintype "bidirectional"))
      (node (ref "C17") (pin "2") (pinfunction "2_2") (pintype "bidirectional"))
      (node (ref "C18") (pin "2") (pinfunction "2_2") (pintype "bidirectional"))
      (node (ref "C19") (pin "2") (pinfunction "2_2") (pintype "bidirectional"))
      (node (ref "C2") (pin "2") (pinfunction "2_2") (pintype "bidirectional"))
      (node (ref "C20") (pin "2") (pinfunction "2_2") (pintype "bidirectional"))
      (node (ref "C22") (pin "2") (pinfunction "2_2") (pintype "bidirectional"))
      (node (ref "C23") (pin "2") (pinfunction "2_2") (pintype "bidirectional"))
      (node (ref "C24") (pin "2") (pinfunction "2_2") (pintype "bidirectional"))
      (node (ref "C25") (pin "2") (pinfunction "2_2") (pintype "bidirectional"))
      (node (ref "C26") (pin "2") (pinfunction "2_2") (pintype "bidirectional"))
      (node (ref "C27") (pin "2") (pinfunction "2_2") (pintype "bidirectional"))
      (node (ref "C28") (pin "2") (pinfunction "2_2") (pintype "bidirectional"))
      (node (ref "C29") (pin "2") (pinfunction "2_2") (pintype "bidirectional"))
      (node (ref "C3") (pin "1") (pinfunction "1_1") (pintype "bidirectional"))
      (node (ref "C30") (pin "2") (pinfunction "2_2") (pintype "bidirectional"))
      (node (ref "C31") (pin "2") (pinfunction "2_2") (pintype "bidirectional"))
      (node (ref "C32") (pin "2") (pinfunction "2_2") (pintype "bidirectional"))
      (node (ref "C33") (pin "2") (pinfunction "2_2") (pintype "bidirectional"))
      (node (ref "C34") (pin "2") (pinfunction "2_2") (pintype "bidirectional"))
      (node (ref "C4") (pin "1") (pinfunction "1_1") (pintype "bidirectional"))
      (node (ref "C5") (pin "1") (pinfunction "1_1") (pintype "bidirectional"))
      (node (ref "C6") (pin "1") (pinfunction "1_1") (pintype "bidirectional"))
      (node (ref "C7") (pin "2") (pinfunction "2_2") (pintype "bidirectional"))
      (node (ref "C8") (pin "2") (pinfunction "2_2") (pintype "bidirectional"))
      (node (ref "C9") (pin "2") (pinfunction "2_2") (pintype "bidirectional"))
      (node (ref "D1") (pin "-") (pinfunction "V-_-") (pintype "bidirectional"))
      (node (ref "J1") (pin "5") (pinfunction "GND_5") (pintype "bidirectional"))
      (node (ref "R13") (pin "1") (pinfunction "1_1") (pintype "passive"))
      (node (ref "R18") (pin "1") (pinfunction "1_1") (pintype "passive"))
      (node (ref "R21") (pin "1") (pinfunction "1_1") (pintype "passive"))
      (node (ref "S1") (pin "1") (pinfunction "P$1_1") (pintype "passive"))
      (node (ref "TP27") (pin "P$1") (pinfunction "TESTPOINT_P$1") (pintype "bidirectional"))
      (node (ref "U1") (pin "10") (pinfunction "EXTI_10") (pintype "bidirectional"))
      (node (ref "U1") (pin "GND") (pinfunction "VSS_GND") (pintype "bidirectional"))
      (node (ref "U10") (pin "AD2") (pinfunction "VBUS_AD2") (pintype "bidirectional"))
      (node (ref "U10") (pin "B7") (pinfunction "VSS_B7") (pintype "bidirectional"))
      (node (ref "U10") (pin "F23") (pinfunction "VSS_PA_F23") (pintype "bidirectional"))
      (node (ref "U10") (pin "GND") (pinfunction "VSS_GND") (pintype "bidirectional"))
      (node (ref "U11") (pin "2") (pinfunction "GND_2") (pintype "bidirectional"))
      (node (ref "U2") (pin "1") (pinfunction "GND_1") (pintype "bidirectional"))
      (node (ref "U2") (pin "15") (pinfunction "GND_15") (pintype "bidirectional"))
      (node (ref "U2") (pin "16") (pinfunction "GND_16") (pintype "bidirectional"))
      (node (ref "U2") (pin "17") (pinfunction "GND_17") (pintype "bidirectional"))
      (node (ref "U2") (pin "5") (pinfunction "~{EN}_5") (pintype "bidirectional"))
      (node (ref "U2") (pin "6") (pinfunction "GND_6") (pintype "bidirectional"))
      (node (ref "U2") (pin "PAD") (pinfunction "GND_PAD") (pintype "bidirectional"))
      (node (ref "U3") (pin "GND") (pinfunction "GND_GND") (pintype "bidirectional"))
      (node (ref "U4") (pin "3") (pinfunction "GND_3") (pintype "bidirectional"))
      (node (ref "U4") (pin "5") (pinfunction "GND_5") (pintype "bidirectional"))
      (node (ref "U5") (pin "5") (pinfunction "GND_5") (pintype "bidirectional"))
      (node (ref "U6") (pin "5") (pinfunction "GND_5") (pintype "bidirectional"))
      (node (ref "U6") (pin "6") (pinfunction "GND_6") (pintype "bidirectional"))
      (node (ref "U6") (pin "7") (pinfunction "GND_7") (pintype "bidirectional"))
      (node (ref "U6") (pin "8") (pinfunction "GND_8") (pintype "bidirectional"))
      (node (ref "U7") (pin "3") (pinfunction "GND_3") (pintype "bidirectional"))
      (node (ref "U8") (pin "2") (pinfunction "GND_2") (pintype "bidirectional"))
      (node (ref "U8") (pin "3") (pinfunction "A0_3") (pintype "bidirectional"))
      (node (ref "U8") (pin "EP") (pinfunction "GND_EP") (pintype "bidirectional"))
      (node (ref "U9") (pin "4") (pinfunction "GND_4") (pintype "bidirectional"))
      (node (ref "X1") (pin "2") (pinfunction "GND_2") (pintype "bidirectional"))
      (node (ref "X1") (pin "4") (pinfunction "GND_4") (pintype "bidirectional"))
    )
    (net (code "7") (name "LBST") (class "Default")
      (node (ref "L5") (pin "P$1") (pinfunction "1_P$1") (pintype "bidirectional"))
      (node (ref "U10") (pin "AC15") (pinfunction "P0.19_AC15") (pintype "bidirectional"))
      (node (ref "U2") (pin "20") (pinfunction "LBST_20") (pintype "bidirectional"))
    )
    (net (code "8") (name "LED_BLUE") (class "Default")
      (node (ref "R3") (pin "2") (pinfunction "2_2") (pintype "passive"))
      (node (ref "U10") (pin "K2") (pinfunction "P0.05/AIN3_K2") (pintype "bidirectional"))
    )
    (net (code "9") (name "LED_GREEN") (class "Default")
      (node (ref "R2") (pin "2") (pinfunction "2_2") (pintype "passive"))
      (node (ref "U10") (pin "L1") (pinfunction "P0.06_L1") (pintype "bidirectional"))
    )
    (net (code "10") (name "LED_RED") (class "Default")
      (node (ref "R1") (pin "2") (pinfunction "2_2") (pintype "passive"))
      (node (ref "U10") (pin "J1") (pinfunction "P0.04/AIN2_J1") (pintype "bidirectional"))
    )
    (net (code "11") (name "MISO") (class "Default")
      (node (ref "TP4") (pin "P$1") (pinfunction "TESTPOINT_P$1") (pintype "bidirectional"))
      (node (ref "U1") (pin "6") (pinfunction "SDO_6") (pintype "bidirectional"))
      (node (ref "U10") (pin "R1") (pinfunction "P1.09_R1") (pintype "bidirectional"))
      (node (ref "U6") (pin "3") (pinfunction "MISO/SA0_3") (pintype "bidirectional"))
    )
    (net (code "12") (name "MOSI") (class "Default")
      (node (ref "TP5") (pin "P$1") (pinfunction "TESTPOINT_P$1") (pintype "bidirectional"))
      (node (ref "U1") (pin "9") (pinfunction "SDI_9") (pintype "bidirectional"))
      (node (ref "U10") (pin "N1") (pinfunction "P0.08_N1") (pintype "bidirectional"))
      (node (ref "U6") (pin "4") (pinfunction "MOSI/SDA_4") (pintype "bidirectional"))
    )
    (net (code "13") (name "Net-(A2-ANTENNA)") (class "Default")
      (node (ref "A2") (pin "S1") (pinfunction "ANTENNA_S1") (pintype "bidirectional"))
      (node (ref "C2") (pin "1") (pinfunction "1_1") (pintype "bidirectional"))
      (node (ref "L1") (pin "1") (pinfunction "1_1") (pintype "bidirectional"))
    )
    (net (code "14") (name "Net-(D2-B)") (class "Default")
      (node (ref "D2") (pin "3") (pinfunction "B_3") (pintype "output"))
      (node (ref "R3") (pin "1") (pinfunction "1_1") (pintype "passive"))
    )
    (net (code "15") (name "Net-(D2-G)") (class "Default")
      (node (ref "D2") (pin "4") (pinfunction "G_4") (pintype "output"))
      (node (ref "R2") (pin "1") (pinfunction "1_1") (pintype "passive"))
    )
    (net (code "16") (name "Net-(D2-R)") (class "Default")
      (node (ref "D2") (pin "2") (pinfunction "R_2") (pintype "output"))
      (node (ref "R1") (pin "1") (pinfunction "1_1") (pintype "passive"))
    )
    (net (code "17") (name "Net-(L2-Pad2)") (class "Default")
      (node (ref "L2") (pin "2") (pinfunction "2_2") (pintype "bidirectional"))
      (node (ref "L4") (pin "1") (pinfunction "1_1") (pintype "bidirectional"))
    )
    (net (code "18") (name "Net-(Q1A-D)") (class "Default")
      (node (ref "Q1") (pin "6") (pinfunction "D_6") (pintype "passive"))
      (node (ref "U9") (pin "3") (pinfunction "SCL_3") (pintype "bidirectional"))
    )
    (net (code "19") (name "Net-(Q1B-D)") (class "Default")
      (node (ref "Q1") (pin "3") (pinfunction "D_3") (pintype "passive"))
      (node (ref "U9") (pin "2") (pinfunction "SDA_2") (pintype "bidirectional"))
    )
    (net (code "20") (name "Net-(Q2A-D)") (class "Default")
      (node (ref "Q2") (pin "6") (pinfunction "D_6") (pintype "passive"))
      (node (ref "U11") (pin "6") (pinfunction "SCL_6") (pintype "bidirectional"))
    )
    (net (code "21") (name "Net-(Q2B-D)") (class "Default")
      (node (ref "Q2") (pin "3") (pinfunction "D_3") (pintype "passive"))
      (node (ref "U11") (pin "1") (pinfunction "SDA_1") (pintype "bidirectional"))
    )
    (net (code "22") (name "Net-(Q3A-D)") (class "Default")
      (node (ref "Q3") (pin "6") (pinfunction "D_6") (pintype "passive"))
      (node (ref "U8") (pin "5") (pinfunction "SCL_5") (pintype "bidirectional"))
    )
    (net (code "23") (name "Net-(Q3B-D)") (class "Default")
      (node (ref "Q3") (pin "3") (pinfunction "D_3") (pintype "passive"))
      (node (ref "U8") (pin "6") (pinfunction "SDA_6") (pintype "bidirectional"))
    )
    (net (code "24") (name "Net-(Q4A-D)") (class "Default")
      (node (ref "Q4") (pin "6") (pinfunction "D_6") (pintype "passive"))
      (node (ref "U4") (pin "2") (pinfunction "SCL_2") (pintype "bidirectional"))
    )
    (net (code "25") (name "Net-(Q4B-D)") (class "Default")
      (node (ref "Q4") (pin "3") (pinfunction "D_3") (pintype "passive"))
      (node (ref "U4") (pin "8") (pinfunction "SDA_8") (pintype "bidirectional"))
    )
    (net (code "26") (name "Net-(Q5A-D)") (class "Default")
      (node (ref "C11") (pin "1") (pinfunction "1_1") (pintype "bidirectional"))
      (node (ref "C28") (pin "1") (pinfunction "1_1") (pintype "bidirectional"))
      (node (ref "Q5") (pin "6") (pinfunction "D_6") (pintype "passive"))
      (node (ref "U2") (pin "19") (pinfunction "VSTOR_19") (pintype "bidirectional"))
      (node (ref "U2") (pin "3") (pinfunction "VOC_SAMP_3") (pintype "bidirectional"))
    )
    (net (code "27") (name "Net-(Q5A-G)") (class "Default")
      (node (ref "Q5") (pin "2") (pinfunction "G_2") (pintype "passive"))
      (node (ref "Q5") (pin "5") (pinfunction "G_5") (pintype "passive"))
      (node (ref "U2") (pin "9") (pinfunction "~{VBAT_SEC_ON}_9") (pintype "bidirectional"))
    )
    (net (code "28") (name "Net-(Q5A-S)") (class "Default")
      (node (ref "Q5") (pin "1") (pinfunction "S_1") (pintype "passive"))
      (node (ref "Q5") (pin "4") (pinfunction "S_4") (pintype "passive"))
    )
    (net (code "29") (name "Net-(Q6A-G)") (class "Default")
      (node (ref "Q6") (pin "2") (pinfunction "G_2") (pintype "passive"))
      (node (ref "Q6") (pin "5") (pinfunction "G_5") (pintype "passive"))
      (node (ref "U2") (pin "10") (pinfunction "~{VBAT_PRI_ON}_10") (pintype "bidirectional"))
    )
    (net (code "30") (name "Net-(Q6A-S)") (class "Default")
      (node (ref "Q6") (pin "1") (pinfunction "S_1") (pintype "passive"))
      (node (ref "Q6") (pin "4") (pinfunction "S_4") (pintype "passive"))
    )
    (net (code "31") (name "Net-(Q7B-D)") (class "Default")
      (node (ref "Q7") (pin "3") (pinfunction "D_3") (pintype "passive"))
      (node (ref "U8") (pin "1") (pinfunction "VCC_1") (pintype "bidirectional"))
    )
    (net (code "32") (name "Net-(Q8A-D)") (class "Default")
      (node (ref "Q8") (pin "6") (pinfunction "D_6") (pintype "passive"))
      (node (ref "U9") (pin "1") (pinfunction "VDD_1") (pintype "bidirectional"))
    )
    (net (code "33") (name "Net-(Q8B-D)") (class "Default")
      (node (ref "Q8") (pin "3") (pinfunction "D_3") (pintype "passive"))
      (node (ref "U11") (pin "5") (pinfunction "VCC_5") (pintype "bidirectional"))
    )
    (net (code "34") (name "Net-(Q10A-D)") (class "Default")
      (node (ref "Q10") (pin "6") (pinfunction "D_6") (pintype "passive"))
      (node (ref "U3") (pin "VCC") (pinfunction "VCC_VCC") (pintype "bidirectional"))
    )
    (net (code "35") (name "Net-(S1-P$2)") (class "Default")
      (node (ref "R10") (pin "1") (pinfunction "1_1") (pintype "passive"))
      (node (ref "S1") (pin "2") (pinfunction "P$2_2") (pintype "passive"))
      (node (ref "U1") (pin "3") (pinfunction "~{EXTR}_3") (pintype "bidirectional"))
    )
    (net (code "36") (name "Net-(U1-AF)") (class "Default")
      (node (ref "C7") (pin "1") (pinfunction "1_1") (pintype "bidirectional"))
      (node (ref "U1") (pin "14") (pinfunction "AF_14") (pintype "bidirectional"))
    )
    (net (code "37") (name "Net-(U1-XI)") (class "Default")
      (node (ref "C33") (pin "1") (pinfunction "1_1") (pintype "bidirectional"))
      (node (ref "U1") (pin "16") (pinfunction "XI_16") (pintype "bidirectional"))
      (node (ref "X4") (pin "1") (pinfunction "1_1") (pintype "bidirectional"))
    )
    (net (code "38") (name "Net-(U1-XO)") (class "Default")
      (node (ref "C34") (pin "1") (pinfunction "1_1") (pintype "bidirectional"))
      (node (ref "U1") (pin "15") (pinfunction "XO_15") (pintype "bidirectional"))
      (node (ref "X4") (pin "2") (pinfunction "2_2") (pintype "bidirectional"))
    )
    (net (code "39") (name "Net-(U2-OK_HYST)") (class "Default")
      (node (ref "R17") (pin "2") (pinfunction "2_2") (pintype "passive"))
      (node (ref "R4") (pin "1") (pinfunction "1_1") (pintype "passive"))
      (node (ref "U2") (pin "11") (pinfunction "OK_HYST_11") (pintype "bidirectional"))
    )
    (net (code "40") (name "Net-(U2-OK_PROG)") (class "Default")
      (node (ref "R17") (pin "1") (pinfunction "1_1") (pintype "passive"))
      (node (ref "R18") (pin "2") (pinfunction "2_2") (pintype "passive"))
      (node (ref "U2") (pin "12") (pinfunction "OK_PROG_12") (pintype "bidirectional"))
    )
    (net (code "41") (name "Net-(U2-VBAT_OV)") (class "Default")
      (node (ref "R14") (pin "1") (pinfunction "1_1") (pintype "passive"))
      (node (ref "R21") (pin "2") (pinfunction "2_2") (pintype "passive"))
      (node (ref "U2") (pin "7") (pinfunction "VBAT_OV_7") (pintype "bidirectional"))
    )
    (net (code "42") (name "Net-(U2-VRDIV)") (class "Default")
      (node (ref "R14") (pin "2") (pinfunction "2_2") (pintype "passive"))
      (node (ref "R4") (pin "2") (pinfunction "2_2") (pintype "passive"))
      (node (ref "U2") (pin "8") (pinfunction "VRDIV_8") (pintype "bidirectional"))
    )
    (net (code "43") (name "Net-(U2-VREF_SAMP)") (class "Default")
      (node (ref "C10") (pin "1") (pinfunction "1_1") (pintype "bidirectional"))
      (node (ref "U2") (pin "4") (pinfunction "VREF_SAMP_4") (pintype "bidirectional"))
    )
    (net (code "44") (name "Net-(U4-VDD)") (class "Default")
      (node (ref "U4") (pin "1") (pinfunction "VDD_1") (pintype "bidirectional"))
      (node (ref "U5") (pin "3") (pinfunction "VOUT_3") (pintype "bidirectional"))
    )
    (net (code "45") (name "Net-(U7-EN)") (class "Default")
      (node (ref "R22") (pin "1") (pinfunction "1_1") (pintype "passive"))
      (node (ref "U7") (pin "6") (pinfunction "EN_6") (pintype "bidirectional"))
    )
    (net (code "46") (name "Net-(U7-SEL)") (class "Default")
      (node (ref "R13") (pin "2") (pinfunction "2_2") (pintype "passive"))
      (node (ref "U7") (pin "4") (pinfunction "SEL_4") (pintype "bidirectional"))
    )
    (net (code "47") (name "Net-(U10-ANT)") (class "Default")
      (node (ref "C1") (pin "1") (pinfunction "1_1") (pintype "bidirectional"))
      (node (ref "L1") (pin "2") (pinfunction "2_2") (pintype "bidirectional"))
      (node (ref "U10") (pin "H23") (pinfunction "ANT_H23") (pintype "bidirectional"))
    )
    (net (code "48") (name "Net-(U10-DCC)") (class "Default")
      (node (ref "L4") (pin "2") (pinfunction "2_2") (pintype "bidirectional"))
      (node (ref "U10") (pin "B3") (pinfunction "DCC_B3") (pintype "bidirectional"))
    )
    (net (code "49") (name "Net-(U10-DEC1)") (class "Default")
      (node (ref "C15") (pin "1") (pinfunction "1_1") (pintype "bidirectional"))
      (node (ref "U10") (pin "C1") (pinfunction "DEC1_C1") (pintype "bidirectional"))
    )
    (net (code "50") (name "Net-(U10-DEC3)") (class "Default")
      (node (ref "C8") (pin "1") (pinfunction "1_1") (pintype "bidirectional"))
      (node (ref "U10") (pin "D23") (pinfunction "DEC3_D23") (pintype "bidirectional"))
    )
    (net (code "51") (name "Net-(U10-DEC4)") (class "Default")
      (node (ref "C12") (pin "1") (pinfunction "1_1") (pintype "bidirectional"))
      (node (ref "C23") (pin "1") (pinfunction "1_1") (pintype "bidirectional"))
      (node (ref "L2") (pin "1") (pinfunction "1_1") (pintype "bidirectional"))
      (node (ref "U10") (pin "B5") (pinfunction "DEC4_B5") (pintype "bidirectional"))
      (node (ref "U10") (pin "E24") (pinfunction "DEC6_E24") (pintype "bidirectional"))
    )
    (net (code "52") (name "Net-(U10-DEC5)") (class "Default")
      (node (ref "C9") (pin "1") (pinfunction "1_1") (pintype "bidirectional"))
      (node (ref "U10") (pin "N24") (pinfunction "DEC5_N24") (pintype "bidirectional"))
    )
    (net (code "53") (name "Net-(U10-P0.00{slash}XL1)") (class "Default")
      (node (ref "C6") (pin "2") (pinfunction "2_2") (pintype "bidirectional"))
      (node (ref "U10") (pin "D2") (pinfunction "P0.00/XL1_D2") (pintype "bidirectional"))
      (node (ref "X3") (pin "A") (pinfunction "1_A") (pintype "bidirectional"))
    )
    (net (code "54") (name "Net-(U10-P0.01{slash}XL2)") (class "Default")
      (node (ref "C5") (pin "2") (pinfunction "2_2") (pintype "bidirectional"))
      (node (ref "U10") (pin "F2") (pinfunction "P0.01/XL2_F2") (pintype "bidirectional"))
      (node (ref "X3") (pin "B") (pinfunction "2_B") (pintype "bidirectional"))
    )
    (net (code "55") (name "Net-(U10-XC1)") (class "Default")
      (node (ref "C3") (pin "2") (pinfunction "2_2") (pintype "bidirectional"))
      (node (ref "U10") (pin "B24") (pinfunction "XC1_B24") (pintype "bidirectional"))
      (node (ref "X1") (pin "3") (pinfunction "2_3") (pintype "bidirectional"))
    )
    (net (code "56") (name "Net-(U10-XC2)") (class "Default")
      (node (ref "C4") (pin "2") (pinfunction "2_2") (pintype "bidirectional"))
      (node (ref "U10") (pin "A23") (pinfunction "XC2_A23") (pintype "bidirectional"))
      (node (ref "X1") (pin "1") (pinfunction "1_1") (pintype "bidirectional"))
    )
    (net (code "57") (name "PIR_OUT") (class "Default")
      (node (ref "TP22") (pin "P$1") (pinfunction "TESTPOINT_P$1") (pintype "bidirectional"))
      (node (ref "U10") (pin "AC11") (pinfunction "P0.16_AC11") (pintype "bidirectional"))
      (node (ref "U3") (pin "OUT") (pinfunction "OUT_OUT") (pintype "bidirectional"))
    )
    (net (code "58") (name "RTC_CS") (class "Default")
      (node (ref "TP6") (pin "P$1") (pinfunction "TESTPOINT_P$1") (pintype "bidirectional"))
      (node (ref "U1") (pin "12") (pinfunction "~{CS}_12") (pintype "bidirectional"))
      (node (ref "U10") (pin "B17") (pinfunction "P1.12_B17") (pintype "bidirectional"))
    )
    (net (code "59") (name "SCK") (class "Default")
      (node (ref "TP3") (pin "P$1") (pinfunction "TESTPOINT_P$1") (pintype "bidirectional"))
      (node (ref "U1") (pin "7") (pinfunction "SCL_7") (pintype "bidirectional"))
      (node (ref "U10") (pin "U1") (pinfunction "P0.12_U1") (pintype "bidirectional"))
      (node (ref "U6") (pin "1") (pinfunction "SCL/SPC_1") (pintype "bidirectional"))
    )
    (net (code "60") (name "SCL") (class "Default")
      (node (ref "Q1") (pin "1") (pinfunction "S_1") (pintype "passive"))
      (node (ref "Q2") (pin "1") (pinfunction "S_1") (pintype "passive"))
      (node (ref "Q3") (pin "1") (pinfunction "S_1") (pintype "passive"))
      (node (ref "Q4") (pin "1") (pinfunction "S_1") (pintype "passive"))
      (node (ref "R6") (pin "1") (pinfunction "1_1") (pintype "passive"))
      (node (ref "TP2") (pin "P$1") (pinfunction "TESTPOINT_P$1") (pintype "bidirectional"))
      (node (ref "U10") (pin "AC9") (pinfunction "P0.14_AC9") (pintype "bidirectional"))
    )
    (net (code "61") (name "SDA") (class "Default")
      (node (ref "Q1") (pin "4") (pinfunction "S_4") (pintype "passive"))
      (node (ref "Q2") (pin "4") (pinfunction "S_4") (pintype "passive"))
      (node (ref "Q3") (pin "4") (pinfunction "S_4") (pintype "passive"))
      (node (ref "Q4") (pin "4") (pinfunction "S_4") (pintype "passive"))
      (node (ref "R7") (pin "1") (pinfunction "1_1") (pintype "passive"))
      (node (ref "TP1") (pin "P$1") (pinfunction "TESTPOINT_P$1") (pintype "bidirectional"))
      (node (ref "U10") (pin "AD10") (pinfunction "P0.15_AD10") (pintype "bidirectional"))
    )
    (net (code "62") (name "SW") (class "Default")
      (node (ref "L3") (pin "P$2") (pinfunction "2_P$2") (pintype "bidirectional"))
      (node (ref "TP25") (pin "P$1") (pinfunction "TESTPOINT_P$1") (pintype "bidirectional"))
      (node (ref "U10") (pin "AD8") (pinfunction "P0.13_AD8") (pintype "bidirectional"))
      (node (ref "U7") (pin "2") (pinfunction "LX_2") (pintype "bidirectional"))
    )
    (net (code "63") (name "SWDCLK") (class "Default")
      (node (ref "J1") (pin "4") (pinfunction "SWDCLK_4") (pintype "bidirectional"))
      (node (ref "U10") (pin "AA24") (pinfunction "SWDCLK_AA24") (pintype "bidirectional"))
    )
    (net (code "64") (name "SWDIO") (class "Default")
      (node (ref "J1") (pin "2") (pinfunction "SWDIO_2") (pintype "bidirectional"))
      (node (ref "U10") (pin "AC24") (pinfunction "SWDIO_AC24") (pintype "bidirectional"))
    )
    (net (code "65") (name "VBAT") (class "Default")
      (node (ref "BAT1") (pin "1") (pinfunction "+_1") (pintype "bidirectional"))
      (node (ref "BAT1") (pin "2") (pinfunction "+_2") (pintype "bidirectional"))
      (node (ref "Q6") (pin "6") (pinfunction "D_6") (pintype "passive"))
      (node (ref "U1") (pin "5") (pinfunction "VBAT_5") (pintype "bidirectional"))
      (node (ref "U10") (pin "A10") (pinfunction "P0.29/AIN5_A10") (pintype "bidirectional"))
      (node (ref "U2") (pin "14") (pinfunction "VBAT_PRI_14") (pintype "bidirectional"))
    )
    (net (code "66") (name "VBAT_OK") (class "Default")
      (node (ref "U10") (pin "R24") (pinfunction "P1.06_R24") (pintype "bidirectional"))
      (node (ref "U2") (pin "13") (pinfunction "VBAT_OK_13") (pintype "bidirectional"))
    )
    (net (code "67") (name "VCC") (class "Default")
      (node (ref "C13") (pin "1") (pinfunction "1_1") (pintype "bidirectional"))
      (node (ref "C14") (pin "1") (pinfunction "1_1") (pintype "bidirectional"))
      (node (ref "C16") (pin "1") (pinfunction "1_1") (pintype "bidirectional"))
      (node (ref "C17") (pin "1") (pinfunction "1_1") (pintype "bidirectional"))
      (node (ref "C18") (pin "1") (pinfunction "1_1") (pintype "bidirectional"))
      (node (ref "C19") (pin "1") (pinfunction "1_1") (pintype "bidirectional"))
      (node (ref "C20") (pin "1") (pinfunction "1_1") (pintype "bidirectional"))
      (node (ref "C22") (pin "1") (pinfunction "1_1") (pintype "bidirectional"))
      (node (ref "C24") (pin "1") (pinfunction "1_1") (pintype "bidirectional"))
      (node (ref "C25") (pin "1") (pinfunction "1_1") (pintype "bidirectional"))
      (node (ref "C26") (pin "1") (pinfunction "1_1") (pintype "bidirectional"))
      (node (ref "C27") (pin "1") (pinfunction "1_1") (pintype "bidirectional"))
      (node (ref "C31") (pin "1") (pinfunction "1_1") (pintype "bidirectional"))
      (node (ref "C32") (pin "1") (pinfunction "1_1") (pintype "bidirectional"))
      (node (ref "D2") (pin "1") (pinfunction "VDD_1") (pintype "bidirectional"))
      (node (ref "J1") (pin "1") (pinfunction "VCC_1") (pintype "bidirectional"))
      (node (ref "Q10") (pin "1") (pinfunction "S_1") (pintype "passive"))
      (node (ref "Q7") (pin "4") (pinfunction "S_4") (pintype "passive"))
      (node (ref "Q8") (pin "1") (pinfunction "S_1") (pintype "passive"))
      (node (ref "Q8") (pin "4") (pinfunction "S_4") (pintype "passive"))
      (node (ref "R10") (pin "2") (pinfunction "2_2") (pintype "passive"))
      (node (ref "R11") (pin "2") (pinfunction "2_2") (pintype "passive"))
      (node (ref "R12") (pin "2") (pinfunction "2_2") (pintype "passive"))
      (node (ref "R23") (pin "2") (pinfunction "2_2") (pintype "passive"))
      (node (ref "R24") (pin "2") (pinfunction "2_2") (pintype "passive"))
      (node (ref "R25") (pin "2") (pinfunction "2_2") (pintype "passive"))
      (node (ref "R26") (pin "2") (pinfunction "2_2") (pintype "passive"))
      (node (ref "R27") (pin "2") (pinfunction "2_2") (pintype "passive"))
      (node (ref "R6") (pin "2") (pinfunction "2_2") (pintype "passive"))
      (node (ref "R7") (pin "2") (pinfunction "2_2") (pintype "passive"))
      (node (ref "R8") (pin "2") (pinfunction "2_2") (pintype "passive"))
      (node (ref "R9") (pin "2") (pinfunction "2_2") (pintype "passive"))
      (node (ref "TP26") (pin "P$1") (pinfunction "TESTPOINT_P$1") (pintype "bidirectional"))
      (node (ref "U1") (pin "13") (pinfunction "VCC_13") (pintype "bidirectional"))
      (node (ref "U10") (pin "A22") (pinfunction "VDD_A22") (pintype "bidirectional"))
      (node (ref "U10") (pin "AD14") (pinfunction "VDD_AD14") (pintype "bidirectional"))
      (node (ref "U10") (pin "AD23") (pinfunction "VDD_AD23") (pintype "bidirectional"))
      (node (ref "U10") (pin "B1") (pinfunction "VDD_B1") (pintype "bidirectional"))
      (node (ref "U10") (pin "W1") (pinfunction "VDD_W1") (pintype "bidirectional"))
      (node (ref "U10") (pin "Y2") (pinfunction "VDDH_Y2") (pintype "bidirectional"))
      (node (ref "U5") (pin "1") (pinfunction "VIN_1") (pintype "bidirectional"))
      (node (ref "U6") (pin "10") (pinfunction "VDD_IO_10") (pintype "bidirectional"))
      (node (ref "U6") (pin "9") (pinfunction "VCC_9") (pintype "bidirectional"))
      (node (ref "U7") (pin "1") (pinfunction "OUT_1") (pintype "bidirectional"))
    )
    (net (code "68") (name "VSEC") (class "Default")
      (node (ref "BT1") (pin "+") (pinfunction "+_+") (pintype "bidirectional"))
      (node (ref "TP24") (pin "P$1") (pinfunction "TESTPOINT_P$1") (pintype "bidirectional"))
      (node (ref "U10") (pin "A8") (pinfunction "P0.31/AIN7_A8") (pintype "bidirectional"))
      (node (ref "U2") (pin "18") (pinfunction "VBAT_SEC_18") (pintype "bidirectional"))
    )
    (net (code "69") (name "VSOL") (class "Default")
      (node (ref "C29") (pin "1") (pinfunction "1_1") (pintype "bidirectional"))
      (node (ref "D1") (pin "+") (pinfunction "V+_+") (pintype "bidirectional"))
      (node (ref "L5") (pin "P$2") (pinfunction "2_P$2") (pintype "bidirectional"))
      (node (ref "TP23") (pin "P$1") (pinfunction "TESTPOINT_P$1") (pintype "bidirectional"))
      (node (ref "U10") (pin "B9") (pinfunction "P0.30/AIN6_B9") (pintype "bidirectional"))
      (node (ref "U2") (pin "2") (pinfunction "VIN_DC_2") (pintype "bidirectional"))
    )
    (net (code "70") (name "VSW") (class "Default")
      (node (ref "C30") (pin "1") (pinfunction "1_1") (pintype "bidirectional"))
      (node (ref "L3") (pin "P$1") (pinfunction "1_P$1") (pintype "bidirectional"))
      (node (ref "Q5") (pin "3") (pinfunction "D_3") (pintype "passive"))
      (node (ref "Q6") (pin "3") (pinfunction "D_3") (pintype "passive"))
      (node (ref "R22") (pin "2") (pinfunction "2_2") (pintype "passive"))
      (node (ref "U7") (pin "5") (pinfunction "IN_5") (pintype "bidirectional"))
    )
    (net (code "71") (name "WDI") (class "Default")
      (node (ref "R12") (pin "1") (pinfunction "1_1") (pintype "passive"))
      (node (ref "TP16") (pin "P$1") (pinfunction "TESTPOINT_P$1") (pintype "bidirectional"))
      (node (ref "U1") (pin "2") (pinfunction "WDI_2") (pintype "bidirectional"))
      (node (ref "U10") (pin "A12") (pinfunction "P0.02/AIN0_A12") (pintype "bidirectional"))
    )
    (net (code "72") (name "unconnected-(J1-SWO-Pad6)") (class "Default")
      (node (ref "J1") (pin "6") (pinfunction "SWO_6") (pintype "bidirectional"))
    )
    (net (code "73") (name "unconnected-(U4-GPIO-Pad6)") (class "Default")
      (node (ref "U4") (pin "6") (pinfunction "GPIO_6") (pintype "bidirectional"))
    )
    (net (code "74") (name "unconnected-(U4-LDR-Pad4)") (class "Default")
      (node (ref "U4") (pin "4") (pinfunction "LDR_4") (pintype "bidirectional"))
    )
    (net (code "75") (name "unconnected-(U10-D+-PadAD6)") (class "Default")
      (node (ref "U10") (pin "AD6") (pinfunction "D+_AD6") (pintype "bidirectional"))
    )
    (net (code "76") (name "unconnected-(U10-D--PadAD4)") (class "Default")
      (node (ref "U10") (pin "AD4") (pinfunction "D-_AD4") (pintype "bidirectional"))
    )
    (net (code "77") (name "unconnected-(U10-DCCH-PadAB2)") (class "Default")
      (node (ref "U10") (pin "AB2") (pinfunction "DCCH_AB2") (pintype "bidirectional"))
    )
    (net (code "78") (name "unconnected-(U10-DEC2-PadA18)") (class "Default")
      (node (ref "U10") (pin "A18") (pinfunction "DEC2_A18") (pintype "bidirectional"))
    )
    (net (code "79") (name "unconnected-(U10-DECUSB-PadAC5)") (class "Default")
      (node (ref "U10") (pin "AC5") (pinfunction "DECUSB_AC5") (pintype "bidirectional"))
    )
    (net (code "80") (name "unconnected-(U10-P0.03{slash}AIN1-PadB13)") (class "Default")
      (node (ref "U10") (pin "B13") (pinfunction "P0.03/AIN1_B13") (pintype "bidirectional"))
    )
    (net (code "81") (name "unconnected-(U10-P0.07-PadM2)") (class "Default")
      (node (ref "U10") (pin "M2") (pinfunction "P0.07_M2") (pintype "bidirectional"))
    )
    (net (code "82") (name "unconnected-(U10-P0.09{slash}NFC1-PadL24)") (class "Default")
      (node (ref "U10") (pin "L24") (pinfunction "P0.09/NFC1_L24") (pintype "bidirectional"))
    )
    (net (code "83") (name "unconnected-(U10-P0.10{slash}NFC2-PadJ24)") (class "Default")
      (node (ref "U10") (pin "J24") (pinfunction "P0.10/NFC2_J24") (pintype "bidirectional"))
    )
    (net (code "84") (name "unconnected-(U10-P0.11-PadT2)") (class "Default")
      (node (ref "U10") (pin "T2") (pinfunction "P0.11_T2") (pintype "bidirectional"))
    )
    (net (code "85") (name "unconnected-(U10-P0.28{slash}AIN4-PadB11)") (class "Default")
      (node (ref "U10") (pin "B11") (pinfunction "P0.28/AIN4_B11") (pintype "bidirectional"))
    )
    (net (code "86") (name "unconnected-(U10-P1.01-PadY23)") (class "Default")
      (node (ref "U10") (pin "Y23") (pinfunction "P1.01_Y23") (pintype "bidirectional"))
    )
    (net (code "87") (name "unconnected-(U10-P1.02-PadW24)") (class "Default")
      (node (ref "U10") (pin "W24") (pinfunction "P1.02_W24") (pintype "bidirectional"))
    )
    (net (code "88") (name "unconnected-(U10-P1.03-PadV23)") (class "Default")
      (node (ref "U10") (pin "V23") (pinfunction "P1.03_V23") (pintype "bidirectional"))
    )
    (net (code "89") (name "unconnected-(U10-P1.04-PadU24)") (class "Default")
      (node (ref "U10") (pin "U24") (pinfunction "P1.04_U24") (pintype "bidirectional"))
    )
    (net (code "90") (name "unconnected-(U10-P1.05-PadT23)") (class "Default")
      (node (ref "U10") (pin "T23") (pinfunction "P1.05_T23") (pintype "bidirectional"))
    )
    (net (code "91") (name "unconnected-(U10-P1.07-PadP23)") (class "Default")
      (node (ref "U10") (pin "P23") (pinfunction "P1.07_P23") (pintype "bidirectional"))
    )
    (net (code "92") (name "unconnected-(U10-P1.08-PadP2)") (class "Default")
      (node (ref "U10") (pin "P2") (pinfunction "P1.08_P2") (pintype "bidirectional"))
    )
    (net (code "93") (name "~{CLR_EN}") (class "Default")
      (node (ref "Q4") (pin "2") (pinfunction "G_2") (pintype "passive"))
      (node (ref "Q4") (pin "5") (pinfunction "G_5") (pintype "passive"))
      (node (ref "R23") (pin "1") (pinfunction "1_1") (pintype "passive"))
      (node (ref "TP9") (pin "P$1") (pinfunction "TESTPOINT_P$1") (pintype "bidirectional"))
      (node (ref "U10") (pin "AC21") (pinfunction "P0.25_AC21") (pintype "bidirectional"))
      (node (ref "U5") (pin "2") (pinfunction "~{SHDN}_2") (pintype "bidirectional"))
    )
    (net (code "94") (name "~{CLR_INT}") (class "Default")
      (node (ref "R8") (pin "1") (pinfunction "1_1") (pintype "passive"))
      (node (ref "TP20") (pin "P$1") (pinfunction "TESTPOINT_P$1") (pintype "bidirectional"))
      (node (ref "U10") (pin "AC19") (pinfunction "P0.23_AC19") (pintype "bidirectional"))
      (node (ref "U4") (pin "7") (pinfunction "INT_7") (pintype "bidirectional"))
    )
    (net (code "95") (name "~{HUM_EN}") (class "Default")
      (node (ref "Q2") (pin "2") (pinfunction "G_2") (pintype "passive"))
      (node (ref "Q2") (pin "5") (pinfunction "G_5") (pintype "passive"))
      (node (ref "Q8") (pin "5") (pinfunction "G_5") (pintype "passive"))
      (node (ref "R26") (pin "1") (pinfunction "1_1") (pintype "passive"))
      (node (ref "TP12") (pin "P$1") (pinfunction "TESTPOINT_P$1") (pintype "bidirectional"))
      (node (ref "U10") (pin "A20") (pinfunction "P1.10_A20") (pintype "bidirectional"))
    )
    (net (code "96") (name "~{LT_EN}") (class "Default")
      (node (ref "Q3") (pin "2") (pinfunction "G_2") (pintype "passive"))
      (node (ref "Q3") (pin "5") (pinfunction "G_5") (pintype "passive"))
      (node (ref "Q7") (pin "5") (pinfunction "G_5") (pintype "passive"))
      (node (ref "R24") (pin "1") (pinfunction "1_1") (pintype "passive"))
      (node (ref "TP10") (pin "P$1") (pinfunction "TESTPOINT_P$1") (pintype "bidirectional"))
      (node (ref "U10") (pin "AD20") (pinfunction "P0.24_AD20") (pintype "bidirectional"))
    )
    (net (code "97") (name "~{LT_INT}") (class "Default")
      (node (ref "R9") (pin "1") (pinfunction "1_1") (pintype "passive"))
      (node (ref "TP21") (pin "P$1") (pinfunction "TESTPOINT_P$1") (pintype "bidirectional"))
      (node (ref "U10") (pin "AD22") (pinfunction "P1.00_AD22") (pintype "bidirectional"))
      (node (ref "U8") (pin "4") (pinfunction "~{INT}_4") (pintype "bidirectional"))
    )
    (net (code "98") (name "~{PIR_EN}") (class "Default")
      (node (ref "Q10") (pin "2") (pinfunction "G_2") (pintype "passive"))
      (node (ref "R27") (pin "1") (pinfunction "1_1") (pintype "passive"))
      (node (ref "TP11") (pin "P$1") (pinfunction "TESTPOINT_P$1") (pintype "bidirectional"))
      (node (ref "U10") (pin "AD12") (pinfunction "P0.17_AD12") (pintype "bidirectional"))
    )
    (net (code "99") (name "~{PR_EN}") (class "Default")
      (node (ref "Q1") (pin "2") (pinfunction "G_2") (pintype "passive"))
      (node (ref "Q1") (pin "5") (pinfunction "G_5") (pintype "passive"))
      (node (ref "Q8") (pin "2") (pinfunction "G_2") (pintype "passive"))
      (node (ref "R25") (pin "1") (pinfunction "1_1") (pintype "passive"))
      (node (ref "TP8") (pin "P$1") (pinfunction "TESTPOINT_P$1") (pintype "bidirectional"))
      (node (ref "U10") (pin "B19") (pinfunction "P1.11_B19") (pintype "bidirectional"))
    )
    (net (code "100") (name "~{RST}") (class "Default")
      (node (ref "J1") (pin "3") (pinfunction "~{RESET}_3") (pintype "bidirectional"))
      (node (ref "R11") (pin "1") (pinfunction "1_1") (pintype "passive"))
      (node (ref "TP17") (pin "P$1") (pinfunction "TESTPOINT_P$1") (pintype "bidirectional"))
      (node (ref "U1") (pin "1") (pinfunction "~{RST}_1") (pintype "bidirectional"))
      (node (ref "U10") (pin "AC13") (pinfunction "P0.18_AC13") (pintype "bidirectional"))
    )
    (net (code "101") (name "~{RTC_IRQ1}") (class "Default")
      (node (ref "TP13") (pin "P$1") (pinfunction "TESTPOINT_P$1") (pintype "bidirectional"))
      (node (ref "U1") (pin "11") (pinfunction "FOUT/~{IRQ1}_11") (pintype "bidirectional"))
      (node (ref "U10") (pin "A16") (pinfunction "P1.13_A16") (pintype "bidirectional"))
    )
    (net (code "102") (name "~{RTC_IRQ2}") (class "Default")
      (node (ref "TP14") (pin "P$1") (pinfunction "TESTPOINT_P$1") (pintype "bidirectional"))
      (node (ref "U1") (pin "4") (pinfunction "~{IRQ2}_4") (pintype "bidirectional"))
      (node (ref "U10") (pin "B15") (pinfunction "P1.14_B15") (pintype "bidirectional"))
    )
    (net (code "103") (name "~{RTC_IRQ3}") (class "Default")
      (node (ref "TP15") (pin "P$1") (pinfunction "TESTPOINT_P$1") (pintype "bidirectional"))
      (node (ref "U1") (pin "8") (pinfunction "CLKOUT/~{IRQ3}_8") (pintype "bidirectional"))
      (node (ref "U10") (pin "A14") (pinfunction "P1.15_A14") (pintype "bidirectional"))
    )
  )
)
